# opendeck_mini.net
KiCad netlist of a schematic drawn in EAGLE
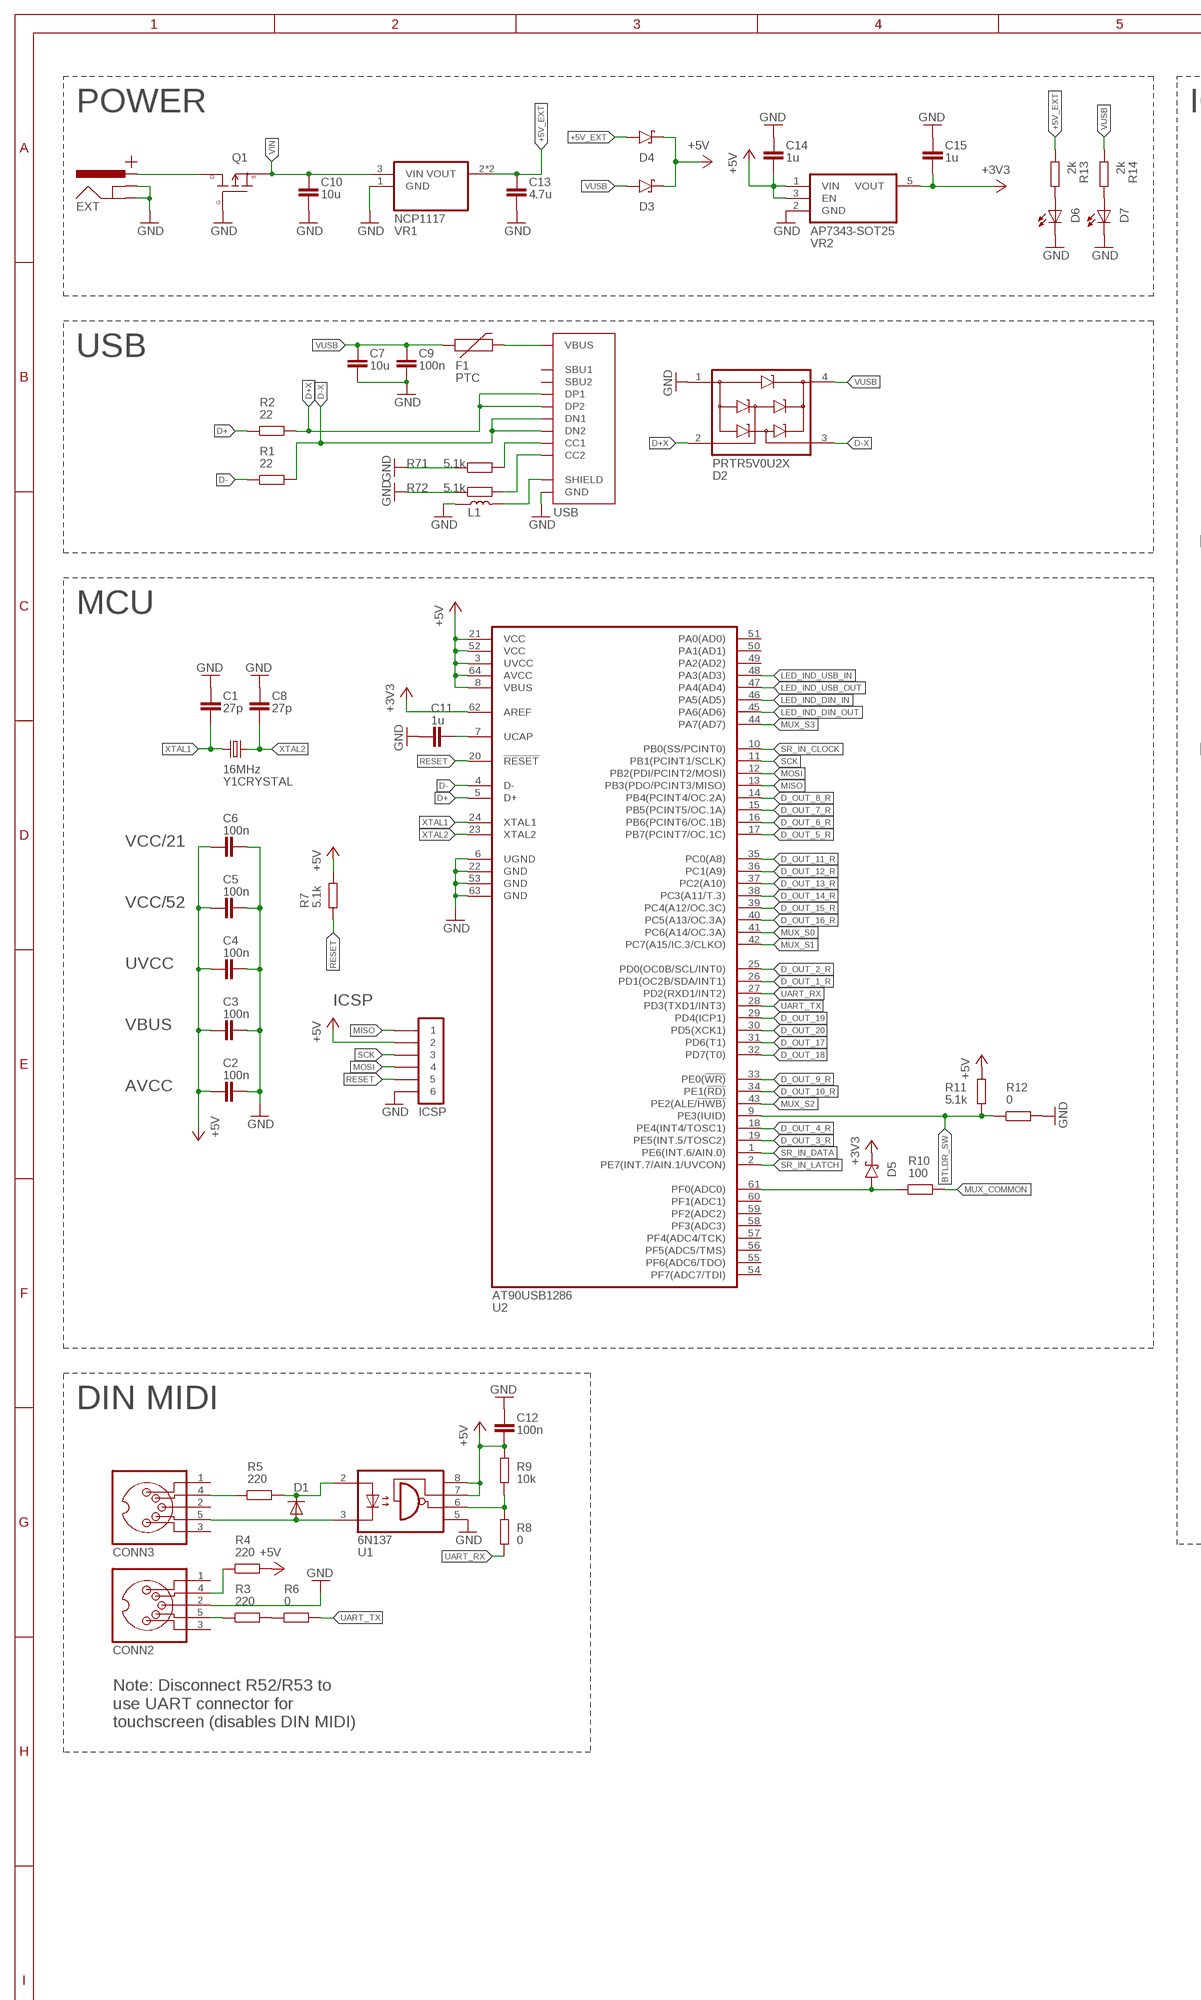
[diagram p0: schematic, sheet 1, part 1 of 2]
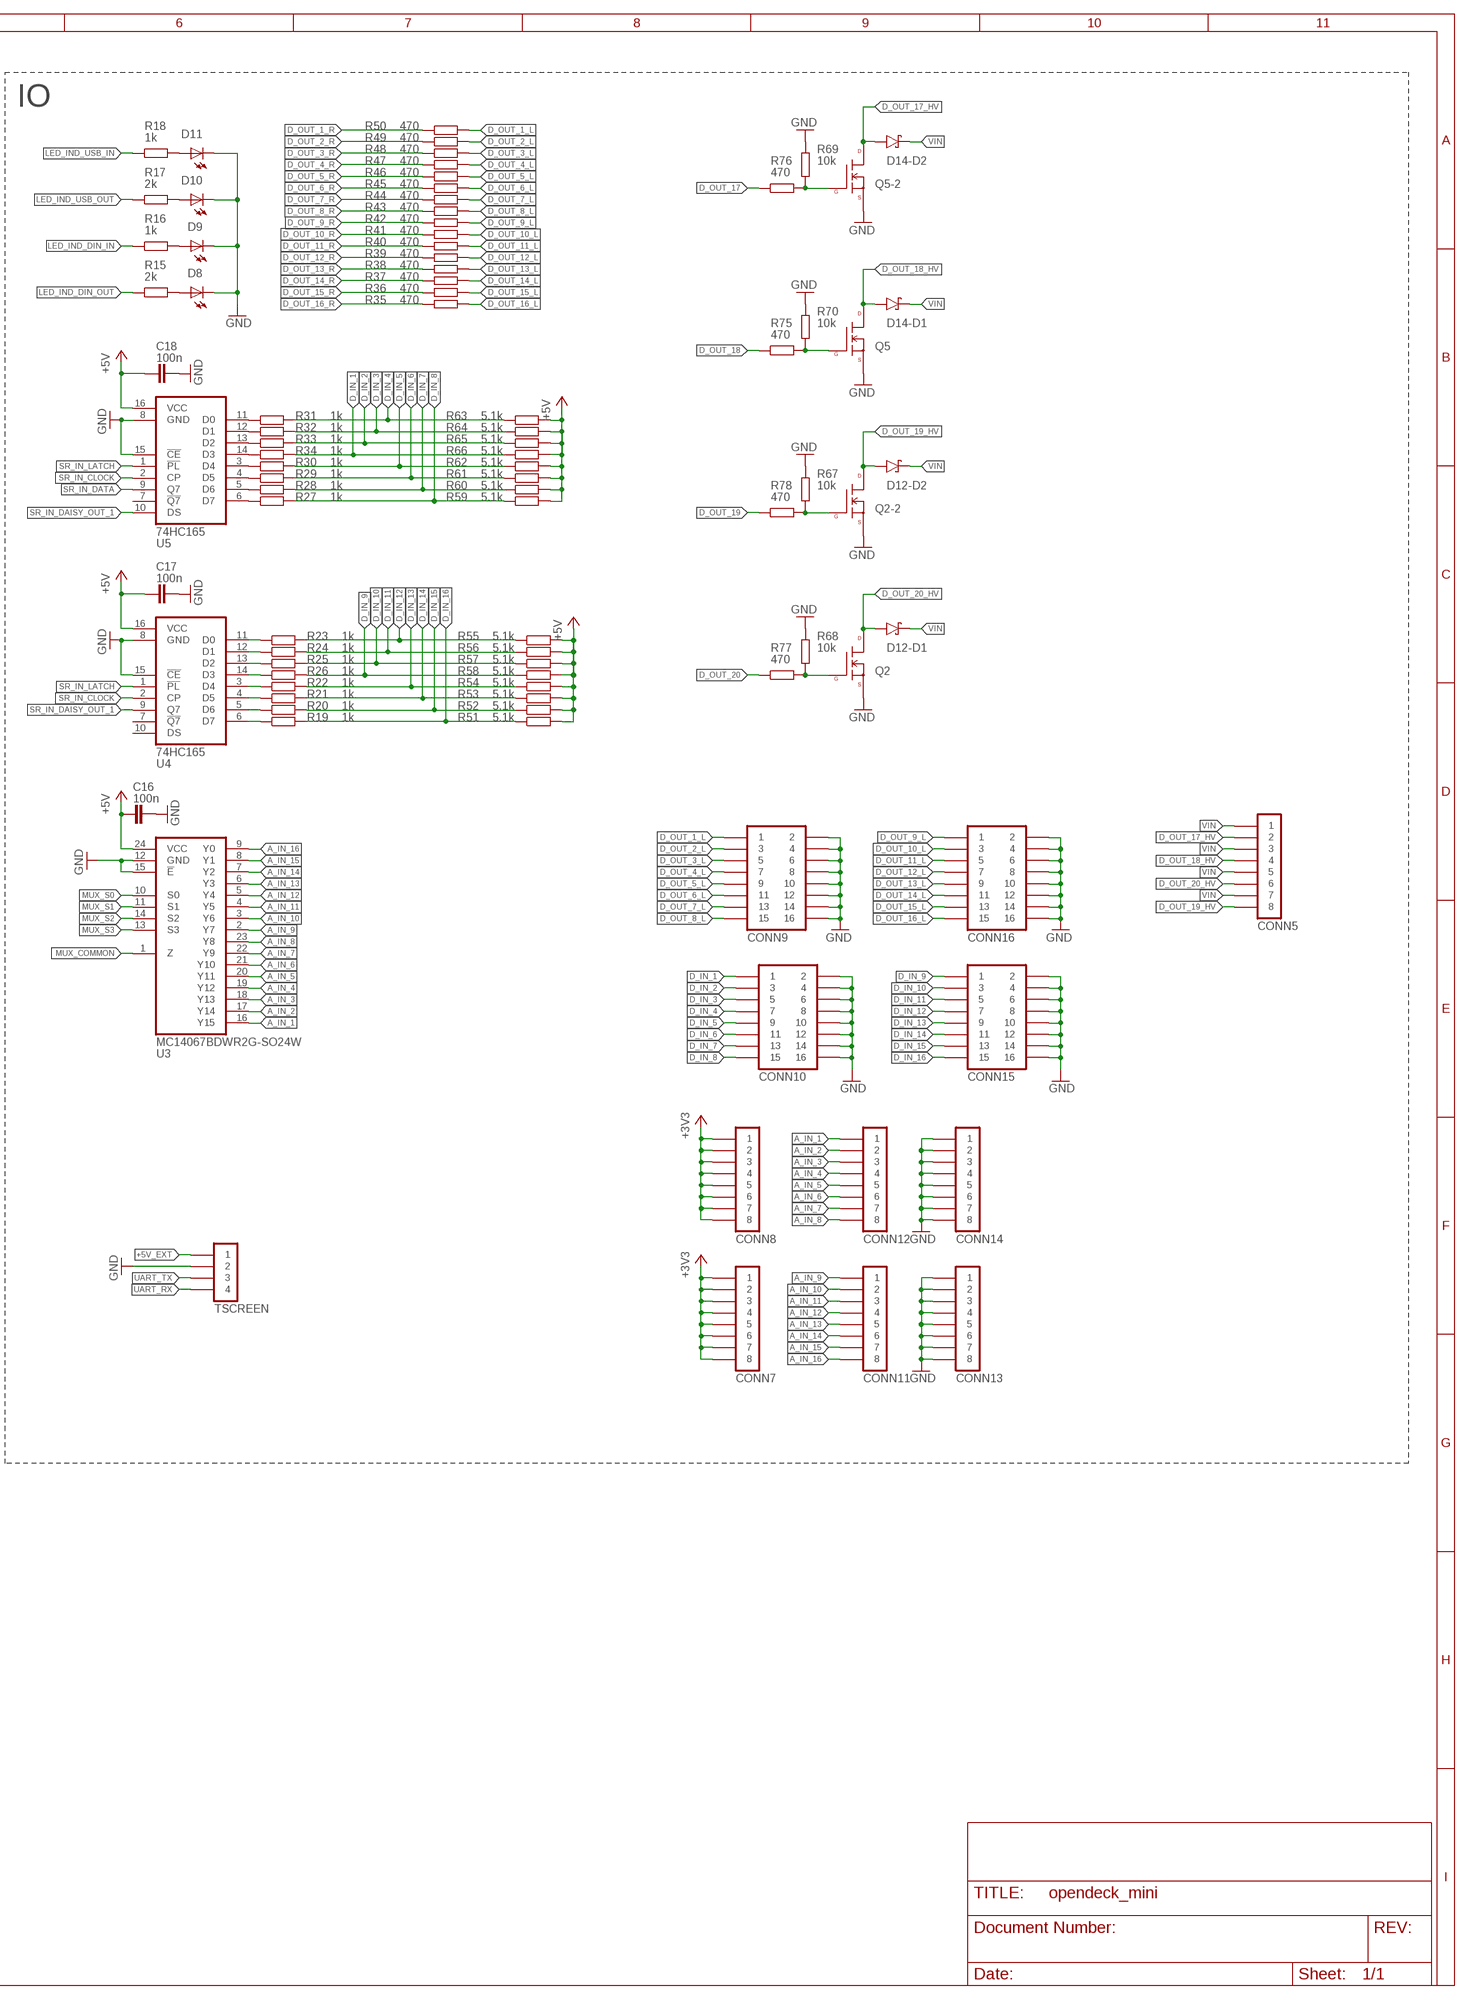
[diagram p1: schematic, sheet 1, part 2 of 2]

(export (version "E")
  (design (tool "Eeschema 10.0.6"))
  (components
    (comp (ref "C1")
      (value "27p")
      (footprint "eagle-import:C0402")
      (libsource (lib "eagle-import") (part "CAPACITOR-0402"))
    )
    (comp (ref "C2")
      (value "100n")
      (footprint "eagle-import:C0402")
      (libsource (lib "eagle-import") (part "CAPACITOR-0402"))
    )
    (comp (ref "C3")
      (value "100n")
      (footprint "eagle-import:C0402")
      (libsource (lib "eagle-import") (part "CAPACITOR-0402"))
    )
    (comp (ref "C4")
      (value "100n")
      (footprint "eagle-import:C0402")
      (libsource (lib "eagle-import") (part "CAPACITOR-0402"))
    )
    (comp (ref "C5")
      (value "100n")
      (footprint "eagle-import:C0402")
      (libsource (lib "eagle-import") (part "CAPACITOR-0402"))
    )
    (comp (ref "C6")
      (value "100n")
      (footprint "eagle-import:C0402")
      (libsource (lib "eagle-import") (part "CAPACITOR-0402"))
    )
    (comp (ref "C7")
      (value "10u")
      (footprint "eagle-import:C0805")
      (libsource (lib "eagle-import") (part "CAPACITOR-0805"))
    )
    (comp (ref "C8")
      (value "27p")
      (footprint "eagle-import:C0402")
      (libsource (lib "eagle-import") (part "CAPACITOR-0402"))
    )
    (comp (ref "C9")
      (value "100n")
      (footprint "eagle-import:C0402")
      (libsource (lib "eagle-import") (part "CAPACITOR-0402"))
    )
    (comp (ref "C10")
      (value "10u")
      (footprint "eagle-import:C0805")
      (libsource (lib "eagle-import") (part "CAPACITOR-0805"))
    )
    (comp (ref "C11")
      (value "1u")
      (footprint "eagle-import:C0603")
      (libsource (lib "eagle-import") (part "CAPACITOR-0603"))
    )
    (comp (ref "C12")
      (value "100n")
      (footprint "eagle-import:C0402")
      (libsource (lib "eagle-import") (part "CAPACITOR-0402"))
    )
    (comp (ref "C13")
      (value "4.7u")
      (footprint "eagle-import:C0603")
      (libsource (lib "eagle-import") (part "CAPACITOR-0603"))
    )
    (comp (ref "C14")
      (value "1u")
      (footprint "eagle-import:C0603")
      (libsource (lib "eagle-import") (part "CAPACITOR-0603"))
    )
    (comp (ref "C15")
      (value "1u")
      (footprint "eagle-import:C0603")
      (libsource (lib "eagle-import") (part "CAPACITOR-0603"))
    )
    (comp (ref "C16")
      (value "100n")
      (footprint "eagle-import:C0402")
      (libsource (lib "eagle-import") (part "CAPACITOR-0402"))
    )
    (comp (ref "C17")
      (value "100n")
      (footprint "eagle-import:C0402")
      (libsource (lib "eagle-import") (part "CAPACITOR-0402"))
    )
    (comp (ref "C18")
      (value "100n")
      (footprint "eagle-import:C0402")
      (libsource (lib "eagle-import") (part "CAPACITOR-0402"))
    )
    (comp (ref "CONN2")
      (value "MIDI_CONN-STD")
      (footprint "eagle-import:DIN5")
      (fields (field (name "MANUFACTURER") "Switchcraft") (field (name "MPN") "57PC5F"))
      (libsource (lib "eagle-import") (part "MIDI_CONN-STD"))
    )
    (comp (ref "CONN3")
      (value "MIDI_CONN-STD")
      (footprint "eagle-import:DIN5")
      (fields (field (name "MANUFACTURER") "Switchcraft") (field (name "MPN") "57PC5F"))
      (libsource (lib "eagle-import") (part "MIDI_CONN-STD"))
    )
    (comp (ref "CONN5")
      (value "PINHD-1X08")
      (footprint "eagle-import:PHOENIX_CONTACT-1984675")
      (fields (field (name "MANUFACTURER") "Phoenix Contact") (field (name "MPN") "1984675"))
      (libsource (lib "eagle-import") (part "PINHD-1X08"))
    )
    (comp (ref "CONN7")
      (value "PINHD-1X08-TH-2.54MM")
      (footprint "eagle-import:1X08-2.54")
      (libsource (lib "eagle-import") (part "PINHD-1X08-TH-2.54MM"))
    )
    (comp (ref "CONN8")
      (value "PINHD-1X08-TH-2.54MM")
      (footprint "eagle-import:1X08-2.54")
      (libsource (lib "eagle-import") (part "PINHD-1X08-TH-2.54MM"))
    )
    (comp (ref "CONN9")
      (value "PINHD-2X08-TH-2.54MM")
      (footprint "eagle-import:2X08-2.54")
      (libsource (lib "eagle-import") (part "PINHD-2X08-TH-2.54MM"))
    )
    (comp (ref "CONN10")
      (value "PINHD-2X08-TH-2.54MM")
      (footprint "eagle-import:2X08-2.54")
      (libsource (lib "eagle-import") (part "PINHD-2X08-TH-2.54MM"))
    )
    (comp (ref "CONN11")
      (value "PINHD-1X08-TH-2.54MM")
      (footprint "eagle-import:1X08-2.54")
      (libsource (lib "eagle-import") (part "PINHD-1X08-TH-2.54MM"))
    )
    (comp (ref "CONN12")
      (value "PINHD-1X08-TH-2.54MM")
      (footprint "eagle-import:1X08-2.54")
      (libsource (lib "eagle-import") (part "PINHD-1X08-TH-2.54MM"))
    )
    (comp (ref "CONN13")
      (value "PINHD-1X08-TH-2.54MM")
      (footprint "eagle-import:1X08-2.54")
      (libsource (lib "eagle-import") (part "PINHD-1X08-TH-2.54MM"))
    )
    (comp (ref "CONN14")
      (value "PINHD-1X08-TH-2.54MM")
      (footprint "eagle-import:1X08-2.54")
      (libsource (lib "eagle-import") (part "PINHD-1X08-TH-2.54MM"))
    )
    (comp (ref "CONN15")
      (value "PINHD-2X08-TH-2.54MM")
      (footprint "eagle-import:2X08-2.54")
      (libsource (lib "eagle-import") (part "PINHD-2X08-TH-2.54MM"))
    )
    (comp (ref "CONN16")
      (value "PINHD-2X08-TH-2.54MM")
      (footprint "eagle-import:2X08-2.54")
      (libsource (lib "eagle-import") (part "PINHD-2X08-TH-2.54MM"))
    )
    (comp (ref "D1")
      (value "1N4148")
      (footprint "eagle-import:SOD-323")
      (fields (field (name "MANUFACTURER") "Comchip Technology") (field (name "MPN") "1N4148WS-HF"))
      (libsource (lib "eagle-import") (part "DIODE-SOD323"))
    )
    (comp (ref "D2")
      (value "PRTR5V0U2X")
      (footprint "eagle-import:SOT143")
      (fields (field (name "MANUFACTURER") "Nexperia"))
      (libsource (lib "eagle-import") (part "PRTR5V0U2X"))
    )
    (comp (ref "D3")
      (value "BAT46INFEON-SOD123")
      (footprint "eagle-import:SOD-123")
      (fields (field (name "MANUFACTURER") "Infineon Technologies") (field (name "MPN") "BAT60AE6327HTSA1"))
      (libsource (lib "eagle-import") (part "BAT46-SOD123INFEON"))
    )
    (comp (ref "D4")
      (value "BAT46INFEON-SOD123")
      (footprint "eagle-import:SOD-123")
      (fields (field (name "MANUFACTURER") "Infineon Technologies") (field (name "MPN") "BAT60AE6327HTSA1"))
      (libsource (lib "eagle-import") (part "BAT46-SOD123INFEON"))
    )
    (comp (ref "D5")
      (value "BAT46-SOT23")
      (footprint "eagle-import:SOT23")
      (fields
        (field (name "MANUFACTURER") "Micro Commercial Components (MCC)")
        (field (name "MPN") "MMBD301-TP")
      )
      (libsource (lib "eagle-import") (part "BAT46-SOT23"))
    )
    (comp (ref "D6")
      (value "Green")
      (footprint "eagle-import:0805_LED")
      (libsource (lib "eagle-import") (part "LED-0805"))
    )
    (comp (ref "D7")
      (value "Blue")
      (footprint "eagle-import:0805_LED")
      (libsource (lib "eagle-import") (part "LED-0805"))
    )
    (comp (ref "D8")
      (value "Red")
      (footprint "eagle-import:0805_LED")
      (libsource (lib "eagle-import") (part "LED-0805"))
    )
    (comp (ref "D9")
      (value "Yellow")
      (footprint "eagle-import:0805_LED")
      (libsource (lib "eagle-import") (part "LED-0805"))
    )
    (comp (ref "D10")
      (value "Red")
      (footprint "eagle-import:0805_LED")
      (libsource (lib "eagle-import") (part "LED-0805"))
    )
    (comp (ref "D11")
      (value "Yellow")
      (footprint "eagle-import:0805_LED")
      (libsource (lib "eagle-import") (part "LED-0805"))
    )
    (comp (ref "D12")
      (value "BAS7007E6327HTSA1")
      (footprint "eagle-import:SOT143")
      (libsource (lib "eagle-import") (part "BAS7007E6327HTSA1"))
    )
    (comp (ref "D14")
      (value "BAS7007E6327HTSA1")
      (footprint "eagle-import:SOT143")
      (libsource (lib "eagle-import") (part "BAS7007E6327HTSA1"))
    )
    (comp (ref "EXT")
      (value "BARREL_JACK")
      (footprint "eagle-import:BARREL_JACK")
      (fields (field (name "MANUFACTURER") "Gravitech") (field (name "MPN") "CON-SOCJ-2155"))
      (libsource (lib "eagle-import") (part "BARREL_JACK"))
    )
    (comp (ref "F1")
      (value "PTC")
      (footprint "eagle-import:L1812")
      (fields (field (name "MANUFACTURER") "Bourns") (field (name "MPN") "MF-MSMF050-2"))
      (libsource (lib "eagle-import") (part "PTC"))
    )
    (comp (ref "ICSP")
      (value "PINHD-2X03-TH-2.54MM-V")
      (footprint "eagle-import:2X03-2.54-V")
      (libsource (lib "eagle-import") (part "PINHD-2X03-TH-2.54MM-V"))
    )
    (comp (ref "L1")
      (value "FERRITE_BEAD-BLM21PG221SN1D")
      (footprint "eagle-import:L0805")
      (fields (field (name "MANUFACTURER") "Murata") (field (name "MPN") "BLM21PG221SN1D"))
      (libsource (lib "eagle-import") (part "FERRITE_BEAD-BLM21PG221SN1D"))
    )
    (comp (ref "Q1")
      (value "BSS314PEH6327XTSA1")
      (footprint "eagle-import:SOT23")
      (fields (field (name "MANUFACTURER") "Infineon Technologies"))
      (libsource (lib "eagle-import") (part "BSS314PEH6327XTSA1"))
    )
    (comp (ref "Q2")
      (value "NTGD3148N")
      (footprint "eagle-import:TSOP-6")
      (fields (field (name "MANUFACTURER") "ON Semiconductor") (field (name "MPN") "NTGD3148NT1G"))
      (libsource (lib "eagle-import") (part "NTGD3148N"))
    )
    (comp (ref "Q5")
      (value "NTGD3148N")
      (footprint "eagle-import:TSOP-6")
      (fields (field (name "MANUFACTURER") "ON Semiconductor") (field (name "MPN") "NTGD3148NT1G"))
      (libsource (lib "eagle-import") (part "NTGD3148N"))
    )
    (comp (ref "R1")
      (value "22")
      (footprint "eagle-import:R0402")
      (libsource (lib "eagle-import") (part "RESISTOR-0402"))
    )
    (comp (ref "R2")
      (value "22")
      (footprint "eagle-import:R0402")
      (libsource (lib "eagle-import") (part "RESISTOR-0402"))
    )
    (comp (ref "R3")
      (value "220")
      (footprint "eagle-import:R0402")
      (libsource (lib "eagle-import") (part "RESISTOR-0402"))
    )
    (comp (ref "R4")
      (value "220")
      (footprint "eagle-import:R0402")
      (libsource (lib "eagle-import") (part "RESISTOR-0402"))
    )
    (comp (ref "R5")
      (value "220")
      (footprint "eagle-import:R0402")
      (libsource (lib "eagle-import") (part "RESISTOR-0402"))
    )
    (comp (ref "R6")
      (value "0")
      (footprint "eagle-import:1X02-2.54-V")
      (libsource (lib "eagle-import") (part "RESISTOR-TH-2.54"))
    )
    (comp (ref "R7")
      (value "5.1k")
      (footprint "eagle-import:R0402")
      (libsource (lib "eagle-import") (part "RESISTOR-0402"))
    )
    (comp (ref "R8")
      (value "0")
      (footprint "eagle-import:1X02-2.54-V")
      (libsource (lib "eagle-import") (part "RESISTOR-TH-2.54"))
    )
    (comp (ref "R9")
      (value "10k")
      (footprint "eagle-import:R0402")
      (libsource (lib "eagle-import") (part "RESISTOR-0402"))
    )
    (comp (ref "R10")
      (value "100")
      (footprint "eagle-import:R0402")
      (libsource (lib "eagle-import") (part "RESISTOR-0402"))
    )
    (comp (ref "R11")
      (value "5.1k")
      (footprint "eagle-import:R0402")
      (libsource (lib "eagle-import") (part "RESISTOR-0402"))
    )
    (comp (ref "R12")
      (value "0")
      (footprint "eagle-import:1X02-2.54-V")
      (libsource (lib "eagle-import") (part "RESISTOR-TH-2.54"))
    )
    (comp (ref "R13")
      (value "2k")
      (footprint "eagle-import:R0402")
      (libsource (lib "eagle-import") (part "RESISTOR-0402"))
    )
    (comp (ref "R14")
      (value "2k")
      (footprint "eagle-import:R0402")
      (libsource (lib "eagle-import") (part "RESISTOR-0402"))
    )
    (comp (ref "R15")
      (value "2k")
      (footprint "eagle-import:R0402")
      (libsource (lib "eagle-import") (part "RESISTOR-0402"))
    )
    (comp (ref "R16")
      (value "1k")
      (footprint "eagle-import:R0402")
      (libsource (lib "eagle-import") (part "RESISTOR-0402"))
    )
    (comp (ref "R17")
      (value "2k")
      (footprint "eagle-import:R0402")
      (libsource (lib "eagle-import") (part "RESISTOR-0402"))
    )
    (comp (ref "R18")
      (value "1k")
      (footprint "eagle-import:R0402")
      (libsource (lib "eagle-import") (part "RESISTOR-0402"))
    )
    (comp (ref "R19")
      (value "1k")
      (footprint "eagle-import:R0402")
      (libsource (lib "eagle-import") (part "RESISTOR-0402"))
    )
    (comp (ref "R20")
      (value "1k")
      (footprint "eagle-import:R0402")
      (libsource (lib "eagle-import") (part "RESISTOR-0402"))
    )
    (comp (ref "R21")
      (value "1k")
      (footprint "eagle-import:R0402")
      (libsource (lib "eagle-import") (part "RESISTOR-0402"))
    )
    (comp (ref "R22")
      (value "1k")
      (footprint "eagle-import:R0402")
      (libsource (lib "eagle-import") (part "RESISTOR-0402"))
    )
    (comp (ref "R23")
      (value "1k")
      (footprint "eagle-import:R0402")
      (libsource (lib "eagle-import") (part "RESISTOR-0402"))
    )
    (comp (ref "R24")
      (value "1k")
      (footprint "eagle-import:R0402")
      (libsource (lib "eagle-import") (part "RESISTOR-0402"))
    )
    (comp (ref "R25")
      (value "1k")
      (footprint "eagle-import:R0402")
      (libsource (lib "eagle-import") (part "RESISTOR-0402"))
    )
    (comp (ref "R26")
      (value "1k")
      (footprint "eagle-import:R0402")
      (libsource (lib "eagle-import") (part "RESISTOR-0402"))
    )
    (comp (ref "R27")
      (value "1k")
      (footprint "eagle-import:R0402")
      (libsource (lib "eagle-import") (part "RESISTOR-0402"))
    )
    (comp (ref "R28")
      (value "1k")
      (footprint "eagle-import:R0402")
      (libsource (lib "eagle-import") (part "RESISTOR-0402"))
    )
    (comp (ref "R29")
      (value "1k")
      (footprint "eagle-import:R0402")
      (libsource (lib "eagle-import") (part "RESISTOR-0402"))
    )
    (comp (ref "R30")
      (value "1k")
      (footprint "eagle-import:R0402")
      (libsource (lib "eagle-import") (part "RESISTOR-0402"))
    )
    (comp (ref "R31")
      (value "1k")
      (footprint "eagle-import:R0402")
      (libsource (lib "eagle-import") (part "RESISTOR-0402"))
    )
    (comp (ref "R32")
      (value "1k")
      (footprint "eagle-import:R0402")
      (libsource (lib "eagle-import") (part "RESISTOR-0402"))
    )
    (comp (ref "R33")
      (value "1k")
      (footprint "eagle-import:R0402")
      (libsource (lib "eagle-import") (part "RESISTOR-0402"))
    )
    (comp (ref "R34")
      (value "1k")
      (footprint "eagle-import:R0402")
      (libsource (lib "eagle-import") (part "RESISTOR-0402"))
    )
    (comp (ref "R35")
      (value "470")
      (footprint "eagle-import:R0402")
      (libsource (lib "eagle-import") (part "RESISTOR-0402"))
    )
    (comp (ref "R36")
      (value "470")
      (footprint "eagle-import:R0402")
      (libsource (lib "eagle-import") (part "RESISTOR-0402"))
    )
    (comp (ref "R37")
      (value "470")
      (footprint "eagle-import:R0402")
      (libsource (lib "eagle-import") (part "RESISTOR-0402"))
    )
    (comp (ref "R38")
      (value "470")
      (footprint "eagle-import:R0402")
      (libsource (lib "eagle-import") (part "RESISTOR-0402"))
    )
    (comp (ref "R39")
      (value "470")
      (footprint "eagle-import:R0402")
      (libsource (lib "eagle-import") (part "RESISTOR-0402"))
    )
    (comp (ref "R40")
      (value "470")
      (footprint "eagle-import:R0402")
      (libsource (lib "eagle-import") (part "RESISTOR-0402"))
    )
    (comp (ref "R41")
      (value "470")
      (footprint "eagle-import:R0402")
      (libsource (lib "eagle-import") (part "RESISTOR-0402"))
    )
    (comp (ref "R42")
      (value "470")
      (footprint "eagle-import:R0402")
      (libsource (lib "eagle-import") (part "RESISTOR-0402"))
    )
    (comp (ref "R43")
      (value "470")
      (footprint "eagle-import:R0402")
      (libsource (lib "eagle-import") (part "RESISTOR-0402"))
    )
    (comp (ref "R44")
      (value "470")
      (footprint "eagle-import:R0402")
      (libsource (lib "eagle-import") (part "RESISTOR-0402"))
    )
    (comp (ref "R45")
      (value "470")
      (footprint "eagle-import:R0402")
      (libsource (lib "eagle-import") (part "RESISTOR-0402"))
    )
    (comp (ref "R46")
      (value "470")
      (footprint "eagle-import:R0402")
      (libsource (lib "eagle-import") (part "RESISTOR-0402"))
    )
    (comp (ref "R47")
      (value "470")
      (footprint "eagle-import:R0402")
      (libsource (lib "eagle-import") (part "RESISTOR-0402"))
    )
    (comp (ref "R48")
      (value "470")
      (footprint "eagle-import:R0402")
      (libsource (lib "eagle-import") (part "RESISTOR-0402"))
    )
    (comp (ref "R49")
      (value "470")
      (footprint "eagle-import:R0402")
      (libsource (lib "eagle-import") (part "RESISTOR-0402"))
    )
    (comp (ref "R50")
      (value "470")
      (footprint "eagle-import:R0402")
      (libsource (lib "eagle-import") (part "RESISTOR-0402"))
    )
    (comp (ref "R51")
      (value "5.1k")
      (footprint "eagle-import:R0402")
      (libsource (lib "eagle-import") (part "RESISTOR-0402"))
    )
    (comp (ref "R52")
      (value "5.1k")
      (footprint "eagle-import:R0402")
      (libsource (lib "eagle-import") (part "RESISTOR-0402"))
    )
    (comp (ref "R53")
      (value "5.1k")
      (footprint "eagle-import:R0402")
      (libsource (lib "eagle-import") (part "RESISTOR-0402"))
    )
    (comp (ref "R54")
      (value "5.1k")
      (footprint "eagle-import:R0402")
      (libsource (lib "eagle-import") (part "RESISTOR-0402"))
    )
    (comp (ref "R55")
      (value "5.1k")
      (footprint "eagle-import:R0402")
      (libsource (lib "eagle-import") (part "RESISTOR-0402"))
    )
    (comp (ref "R56")
      (value "5.1k")
      (footprint "eagle-import:R0402")
      (libsource (lib "eagle-import") (part "RESISTOR-0402"))
    )
    (comp (ref "R57")
      (value "5.1k")
      (footprint "eagle-import:R0402")
      (libsource (lib "eagle-import") (part "RESISTOR-0402"))
    )
    (comp (ref "R58")
      (value "5.1k")
      (footprint "eagle-import:R0402")
      (libsource (lib "eagle-import") (part "RESISTOR-0402"))
    )
    (comp (ref "R59")
      (value "5.1k")
      (footprint "eagle-import:R0402")
      (libsource (lib "eagle-import") (part "RESISTOR-0402"))
    )
    (comp (ref "R60")
      (value "5.1k")
      (footprint "eagle-import:R0402")
      (libsource (lib "eagle-import") (part "RESISTOR-0402"))
    )
    (comp (ref "R61")
      (value "5.1k")
      (footprint "eagle-import:R0402")
      (libsource (lib "eagle-import") (part "RESISTOR-0402"))
    )
    (comp (ref "R62")
      (value "5.1k")
      (footprint "eagle-import:R0402")
      (libsource (lib "eagle-import") (part "RESISTOR-0402"))
    )
    (comp (ref "R63")
      (value "5.1k")
      (footprint "eagle-import:R0402")
      (libsource (lib "eagle-import") (part "RESISTOR-0402"))
    )
    (comp (ref "R64")
      (value "5.1k")
      (footprint "eagle-import:R0402")
      (libsource (lib "eagle-import") (part "RESISTOR-0402"))
    )
    (comp (ref "R65")
      (value "5.1k")
      (footprint "eagle-import:R0402")
      (libsource (lib "eagle-import") (part "RESISTOR-0402"))
    )
    (comp (ref "R66")
      (value "5.1k")
      (footprint "eagle-import:R0402")
      (libsource (lib "eagle-import") (part "RESISTOR-0402"))
    )
    (comp (ref "R67")
      (value "10k")
      (footprint "eagle-import:R0402")
      (libsource (lib "eagle-import") (part "RESISTOR-0402"))
    )
    (comp (ref "R68")
      (value "10k")
      (footprint "eagle-import:R0402")
      (libsource (lib "eagle-import") (part "RESISTOR-0402"))
    )
    (comp (ref "R69")
      (value "10k")
      (footprint "eagle-import:R0402")
      (libsource (lib "eagle-import") (part "RESISTOR-0402"))
    )
    (comp (ref "R70")
      (value "10k")
      (footprint "eagle-import:R0402")
      (libsource (lib "eagle-import") (part "RESISTOR-0402"))
    )
    (comp (ref "R71")
      (value "5.1k")
      (footprint "eagle-import:R0402")
      (libsource (lib "eagle-import") (part "RESISTOR-0402"))
    )
    (comp (ref "R72")
      (value "5.1k")
      (footprint "eagle-import:R0402")
      (libsource (lib "eagle-import") (part "RESISTOR-0402"))
    )
    (comp (ref "R75")
      (value "470")
      (footprint "eagle-import:R0402")
      (libsource (lib "eagle-import") (part "RESISTOR-0402"))
    )
    (comp (ref "R76")
      (value "470")
      (footprint "eagle-import:R0402")
      (libsource (lib "eagle-import") (part "RESISTOR-0402"))
    )
    (comp (ref "R77")
      (value "470")
      (footprint "eagle-import:R0402")
      (libsource (lib "eagle-import") (part "RESISTOR-0402"))
    )
    (comp (ref "R78")
      (value "470")
      (footprint "eagle-import:R0402")
      (libsource (lib "eagle-import") (part "RESISTOR-0402"))
    )
    (comp (ref "TSCREEN")
      (value "PINHD-1X04-TH-2.54MM")
      (footprint "eagle-import:1X04-2.54")
      (libsource (lib "eagle-import") (part "PINHD-1X04-TH-2.54MM"))
    )
    (comp (ref "U1")
      (value "6N137")
      (footprint "eagle-import:DIL08")
      (fields (field (name "MANUFACTURER") "Vishay"))
      (libsource (lib "eagle-import") (part "6N137"))
    )
    (comp (ref "U2")
      (value "AT90USB1286")
      (footprint "eagle-import:TQFP-64-14X14")
      (fields (field (name "MANUFACTURER") "Microchip/Atmel") (field (name "MPN") "AT90USB1286-AU"))
      (libsource (lib "eagle-import") (part "AT90USB1286"))
    )
    (comp (ref "U3")
      (value "MC14067BDWR2G-SO24W")
      (footprint "eagle-import:SO24-W")
      (fields (field (name "MANUFACTURER") "ON Semiconductor") (field (name "MPN") "MC14067BDWR2G"))
      (libsource (lib "eagle-import") (part "MC14067BDWR2G-SO24W"))
    )
    (comp (ref "U4")
      (value "74HC165")
      (footprint "eagle-import:SO16")
      (fields (field (name "MANUFACTURER") "Nexperia") (field (name "MPN") "74HC165D"))
      (libsource (lib "eagle-import") (part "74165HC"))
    )
    (comp (ref "U5")
      (value "74HC165")
      (footprint "eagle-import:SO16")
      (fields (field (name "MANUFACTURER") "Nexperia") (field (name "MPN") "74HC165D"))
      (libsource (lib "eagle-import") (part "74165HC"))
    )
    (comp (ref "USB")
      (value "USB-C")
      (footprint "eagle-import:GCT-USB4085-GF-A")
      (fields (field (name "MANUFACTURER") "GCT") (field (name "MPN") "USB4085-GF-A"))
      (libsource (lib "eagle-import") (part "USB-C"))
    )
    (comp (ref "VR1")
      (value "NCP1117")
      (footprint "eagle-import:SOT223")
      (fields (field (name "MANUFACTURER") "ON Semiconductor") (field (name "MPN") "NCP1117ST50T3G"))
      (libsource (lib "eagle-import") (part "NCP1117"))
    )
    (comp (ref "VR2")
      (value "AP7343-SOT25")
      (footprint "eagle-import:SOT25")
      (fields (field (name "MANUFACTURER") "Diodes Incorporated") (field (name "MPN") "AP7343-33W5-7"))
      (libsource (lib "eagle-import") (part "AP7343-SOT25"))
    )
    (comp (ref "Y1")
      (value "16MHz")
      (footprint "eagle-import:CRYSTAL-SMD-3.2X2.5")
      (fields (field (name "MANUFACTURER") "Epson") (field (name "MPN") "X1E0000210120 TSX-3225 16MHZ 16PF"))
      (libsource (lib "eagle-import") (part "CRYSTAL-4P-SMD-3.2X2.5"))
    )
  )
  (nets
    (net (code "1") (name "+3V3") (class "Default")
      (node (ref "C15") (pin "2") (pinfunction "2_2") (pintype "passive"))
      (node (ref "CONN7") (pin "1") (pinfunction "1_1") (pintype "passive"))
      (node (ref "CONN7") (pin "2") (pinfunction "2_2") (pintype "passive"))
      (node (ref "CONN7") (pin "3") (pinfunction "3_3") (pintype "passive"))
      (node (ref "CONN7") (pin "4") (pinfunction "4_4") (pintype "passive"))
      (node (ref "CONN7") (pin "5") (pinfunction "5_5") (pintype "passive"))
      (node (ref "CONN7") (pin "6") (pinfunction "6_6") (pintype "passive"))
      (node (ref "CONN7") (pin "7") (pinfunction "7_7") (pintype "passive"))
      (node (ref "CONN7") (pin "8") (pinfunction "8_8") (pintype "passive"))
      (node (ref "CONN8") (pin "1") (pinfunction "1_1") (pintype "passive"))
      (node (ref "CONN8") (pin "2") (pinfunction "2_2") (pintype "passive"))
      (node (ref "CONN8") (pin "3") (pinfunction "3_3") (pintype "passive"))
      (node (ref "CONN8") (pin "4") (pinfunction "4_4") (pintype "passive"))
      (node (ref "CONN8") (pin "5") (pinfunction "5_5") (pintype "passive"))
      (node (ref "CONN8") (pin "6") (pinfunction "6_6") (pintype "passive"))
      (node (ref "CONN8") (pin "7") (pinfunction "7_7") (pintype "passive"))
      (node (ref "CONN8") (pin "8") (pinfunction "8_8") (pintype "passive"))
      (node (ref "D5") (pin "3") (pinfunction "C_3") (pintype "passive"))
      (node (ref "U2") (pin "62") (pinfunction "AREF_62") (pintype "power_in"))
      (node (ref "VR2") (pin "5") (pinfunction "VOUT_5") (pintype "passive"))
    )
    (net (code "2") (name "+5V") (class "Default")
      (node (ref "C12") (pin "2") (pinfunction "2_2") (pintype "passive"))
      (node (ref "C14") (pin "2") (pinfunction "2_2") (pintype "passive"))
      (node (ref "C16") (pin "1") (pinfunction "1_1") (pintype "passive"))
      (node (ref "C17") (pin "1") (pinfunction "1_1") (pintype "passive"))
      (node (ref "C18") (pin "1") (pinfunction "1_1") (pintype "passive"))
      (node (ref "C2") (pin "1") (pinfunction "1_1") (pintype "passive"))
      (node (ref "C3") (pin "1") (pinfunction "1_1") (pintype "passive"))
      (node (ref "C4") (pin "1") (pinfunction "1_1") (pintype "passive"))
      (node (ref "C5") (pin "1") (pinfunction "1_1") (pintype "passive"))
      (node (ref "C6") (pin "1") (pinfunction "1_1") (pintype "passive"))
      (node (ref "D3") (pin "C") (pinfunction "C_C") (pintype "passive"))
      (node (ref "D4") (pin "C") (pinfunction "C_C") (pintype "passive"))
      (node (ref "ICSP") (pin "2") (pinfunction "2_2") (pintype "passive"))
      (node (ref "R11") (pin "2") (pinfunction "2_2") (pintype "passive"))
      (node (ref "R4") (pin "2") (pinfunction "2_2") (pintype "passive"))
      (node (ref "R51") (pin "2") (pinfunction "2_2") (pintype "passive"))
      (node (ref "R52") (pin "2") (pinfunction "2_2") (pintype "passive"))
      (node (ref "R53") (pin "2") (pinfunction "2_2") (pintype "passive"))
      (node (ref "R54") (pin "2") (pinfunction "2_2") (pintype "passive"))
      (node (ref "R55") (pin "2") (pinfunction "2_2") (pintype "passive"))
      (node (ref "R56") (pin "2") (pinfunction "2_2") (pintype "passive"))
      (node (ref "R57") (pin "2") (pinfunction "2_2") (pintype "passive"))
      (node (ref "R58") (pin "2") (pinfunction "2_2") (pintype "passive"))
      (node (ref "R59") (pin "2") (pinfunction "2_2") (pintype "passive"))
      (node (ref "R60") (pin "2") (pinfunction "2_2") (pintype "passive"))
      (node (ref "R61") (pin "2") (pinfunction "2_2") (pintype "passive"))
      (node (ref "R62") (pin "2") (pinfunction "2_2") (pintype "passive"))
      (node (ref "R63") (pin "2") (pinfunction "2_2") (pintype "passive"))
      (node (ref "R64") (pin "2") (pinfunction "2_2") (pintype "passive"))
      (node (ref "R65") (pin "2") (pinfunction "2_2") (pintype "passive"))
      (node (ref "R66") (pin "2") (pinfunction "2_2") (pintype "passive"))
      (node (ref "R7") (pin "2") (pinfunction "2_2") (pintype "passive"))
      (node (ref "R9") (pin "2") (pinfunction "2_2") (pintype "passive"))
      (node (ref "U1") (pin "7") (pinfunction "VE_7") (pintype "input"))
      (node (ref "U1") (pin "8") (pinfunction "VCC_8") (pintype "power_in"))
      (node (ref "U2") (pin "21") (pinfunction "VCC_21") (pintype "power_in"))
      (node (ref "U2") (pin "3") (pinfunction "UVCC_3") (pintype "power_in"))
      (node (ref "U2") (pin "52") (pinfunction "VCC_52") (pintype "power_in"))
      (node (ref "U2") (pin "64") (pinfunction "AVCC_64") (pintype "power_in"))
      (node (ref "U2") (pin "8") (pinfunction "VBUS_8") (pintype "power_in"))
      (node (ref "U3") (pin "24") (pinfunction "VCC_24") (pintype "passive"))
      (node (ref "U4") (pin "16") (pinfunction "VCC_16") (pintype "power_in"))
      (node (ref "U5") (pin "16") (pinfunction "VCC_16") (pintype "power_in"))
      (node (ref "VR2") (pin "1") (pinfunction "VIN_1") (pintype "passive"))
      (node (ref "VR2") (pin "3") (pinfunction "EN_3") (pintype "passive"))
    )
    (net (code "3") (name "+5V_EXT") (class "Default")
      (node (ref "C13") (pin "1") (pinfunction "1_1") (pintype "passive"))
      (node (ref "D4") (pin "A") (pinfunction "A_A") (pintype "passive"))
      (node (ref "R13") (pin "1") (pinfunction "1_1") (pintype "passive"))
      (node (ref "TSCREEN") (pin "1") (pinfunction "1_1") (pintype "passive"))
      (node (ref "VR1") (pin "2") (pinfunction "VOUT_2") (pintype "passive"))
      (node (ref "VR1") (pin "4") (pinfunction "VOUT_4") (pintype "passive"))
    )
    (net (code "4") (name "A_IN_1") (class "Default")
      (node (ref "CONN12") (pin "1") (pinfunction "1_1") (pintype "passive"))
      (node (ref "U3") (pin "16") (pinfunction "Y15_16") (pintype "bidirectional"))
    )
    (net (code "5") (name "A_IN_2") (class "Default")
      (node (ref "CONN12") (pin "2") (pinfunction "2_2") (pintype "passive"))
      (node (ref "U3") (pin "17") (pinfunction "Y14_17") (pintype "bidirectional"))
    )
    (net (code "6") (name "A_IN_3") (class "Default")
      (node (ref "CONN12") (pin "3") (pinfunction "3_3") (pintype "passive"))
      (node (ref "U3") (pin "18") (pinfunction "Y13_18") (pintype "bidirectional"))
    )
    (net (code "7") (name "A_IN_4") (class "Default")
      (node (ref "CONN12") (pin "4") (pinfunction "4_4") (pintype "passive"))
      (node (ref "U3") (pin "19") (pinfunction "Y12_19") (pintype "bidirectional"))
    )
    (net (code "8") (name "A_IN_5") (class "Default")
      (node (ref "CONN12") (pin "5") (pinfunction "5_5") (pintype "passive"))
      (node (ref "U3") (pin "20") (pinfunction "Y11_20") (pintype "bidirectional"))
    )
    (net (code "9") (name "A_IN_6") (class "Default")
      (node (ref "CONN12") (pin "6") (pinfunction "6_6") (pintype "passive"))
      (node (ref "U3") (pin "21") (pinfunction "Y10_21") (pintype "bidirectional"))
    )
    (net (code "10") (name "A_IN_7") (class "Default")
      (node (ref "CONN12") (pin "7") (pinfunction "7_7") (pintype "passive"))
      (node (ref "U3") (pin "22") (pinfunction "Y9_22") (pintype "bidirectional"))
    )
    (net (code "11") (name "A_IN_8") (class "Default")
      (node (ref "CONN12") (pin "8") (pinfunction "8_8") (pintype "passive"))
      (node (ref "U3") (pin "23") (pinfunction "Y8_23") (pintype "bidirectional"))
    )
    (net (code "12") (name "A_IN_9") (class "Default")
      (node (ref "CONN11") (pin "1") (pinfunction "1_1") (pintype "passive"))
      (node (ref "U3") (pin "2") (pinfunction "Y7_2") (pintype "bidirectional"))
    )
    (net (code "13") (name "A_IN_10") (class "Default")
      (node (ref "CONN11") (pin "2") (pinfunction "2_2") (pintype "passive"))
      (node (ref "U3") (pin "3") (pinfunction "Y6_3") (pintype "bidirectional"))
    )
    (net (code "14") (name "A_IN_11") (class "Default")
      (node (ref "CONN11") (pin "3") (pinfunction "3_3") (pintype "passive"))
      (node (ref "U3") (pin "4") (pinfunction "Y5_4") (pintype "bidirectional"))
    )
    (net (code "15") (name "A_IN_12") (class "Default")
      (node (ref "CONN11") (pin "4") (pinfunction "4_4") (pintype "passive"))
      (node (ref "U3") (pin "5") (pinfunction "Y4_5") (pintype "bidirectional"))
    )
    (net (code "16") (name "A_IN_13") (class "Default")
      (node (ref "CONN11") (pin "5") (pinfunction "5_5") (pintype "passive"))
      (node (ref "U3") (pin "6") (pinfunction "Y3_6") (pintype "bidirectional"))
    )
    (net (code "17") (name "A_IN_14") (class "Default")
      (node (ref "CONN11") (pin "6") (pinfunction "6_6") (pintype "passive"))
      (node (ref "U3") (pin "7") (pinfunction "Y2_7") (pintype "bidirectional"))
    )
    (net (code "18") (name "A_IN_15") (class "Default")
      (node (ref "CONN11") (pin "7") (pinfunction "7_7") (pintype "passive"))
      (node (ref "U3") (pin "8") (pinfunction "Y1_8") (pintype "bidirectional"))
    )
    (net (code "19") (name "A_IN_16") (class "Default")
      (node (ref "CONN11") (pin "8") (pinfunction "8_8") (pintype "passive"))
      (node (ref "U3") (pin "9") (pinfunction "Y0_9") (pintype "bidirectional"))
    )
    (net (code "20") (name "BTLDR_SW") (class "Default")
      (node (ref "R11") (pin "1") (pinfunction "1_1") (pintype "passive"))
      (node (ref "R12") (pin "1") (pinfunction "1_1") (pintype "passive"))
      (node (ref "U2") (pin "9") (pinfunction "PE3(IUID)_9") (pintype "bidirectional"))
    )
    (net (code "21") (name "D+") (class "Default")
      (node (ref "R2") (pin "1") (pinfunction "1_1") (pintype "passive"))
      (node (ref "U2") (pin "5") (pinfunction "D+_5") (pintype "bidirectional"))
    )
    (net (code "22") (name "D+X") (class "Default")
      (node (ref "D2") (pin "2") (pinfunction "I/O1_2") (pintype "passive"))
      (node (ref "R2") (pin "2") (pinfunction "2_2") (pintype "passive"))
      (node (ref "USB") (pin "A6") (pinfunction "DP1_A6") (pintype "bidirectional"))
      (node (ref "USB") (pin "B6") (pinfunction "DP2_B6") (pintype "bidirectional"))
    )
    (net (code "23") (name "D-") (class "Default")
      (node (ref "R1") (pin "1") (pinfunction "1_1") (pintype "passive"))
      (node (ref "U2") (pin "4") (pinfunction "D-_4") (pintype "bidirectional"))
    )
    (net (code "24") (name "D-X") (class "Default")
      (node (ref "D2") (pin "3") (pinfunction "I/O2_3") (pintype "passive"))
      (node (ref "R1") (pin "2") (pinfunction "2_2") (pintype "passive"))
      (node (ref "USB") (pin "A7") (pinfunction "DN1_A7") (pintype "bidirectional"))
      (node (ref "USB") (pin "B7") (pinfunction "DN2_B7") (pintype "bidirectional"))
    )
    (net (code "25") (name "D_IN_1") (class "Default")
      (node (ref "CONN10") (pin "1") (pinfunction "1_1") (pintype "passive"))
      (node (ref "R34") (pin "2") (pinfunction "2_2") (pintype "passive"))
      (node (ref "R66") (pin "1") (pinfunction "1_1") (pintype "passive"))
    )
    (net (code "26") (name "D_IN_2") (class "Default")
      (node (ref "CONN10") (pin "3") (pinfunction "3_3") (pintype "passive"))
      (node (ref "R33") (pin "2") (pinfunction "2_2") (pintype "passive"))
      (node (ref "R65") (pin "1") (pinfunction "1_1") (pintype "passive"))
    )
    (net (code "27") (name "D_IN_3") (class "Default")
      (node (ref "CONN10") (pin "5") (pinfunction "5_5") (pintype "passive"))
      (node (ref "R32") (pin "2") (pinfunction "2_2") (pintype "passive"))
      (node (ref "R64") (pin "1") (pinfunction "1_1") (pintype "passive"))
    )
    (net (code "28") (name "D_IN_4") (class "Default")
      (node (ref "CONN10") (pin "7") (pinfunction "7_7") (pintype "passive"))
      (node (ref "R31") (pin "2") (pinfunction "2_2") (pintype "passive"))
      (node (ref "R63") (pin "1") (pinfunction "1_1") (pintype "passive"))
    )
    (net (code "29") (name "D_IN_5") (class "Default")
      (node (ref "CONN10") (pin "9") (pinfunction "9_9") (pintype "passive"))
      (node (ref "R30") (pin "2") (pinfunction "2_2") (pintype "passive"))
      (node (ref "R62") (pin "1") (pinfunction "1_1") (pintype "passive"))
    )
    (net (code "30") (name "D_IN_6") (class "Default")
      (node (ref "CONN10") (pin "11") (pinfunction "11_11") (pintype "passive"))
      (node (ref "R29") (pin "2") (pinfunction "2_2") (pintype "passive"))
      (node (ref "R61") (pin "1") (pinfunction "1_1") (pintype "passive"))
    )
    (net (code "31") (name "D_IN_7") (class "Default")
      (node (ref "CONN10") (pin "13") (pinfunction "13_13") (pintype "passive"))
      (node (ref "R28") (pin "2") (pinfunction "2_2") (pintype "passive"))
      (node (ref "R60") (pin "1") (pinfunction "1_1") (pintype "passive"))
    )
    (net (code "32") (name "D_IN_8") (class "Default")
      (node (ref "CONN10") (pin "15") (pinfunction "15_15") (pintype "passive"))
      (node (ref "R27") (pin "2") (pinfunction "2_2") (pintype "passive"))
      (node (ref "R59") (pin "1") (pinfunction "1_1") (pintype "passive"))
    )
    (net (code "33") (name "D_IN_9") (class "Default")
      (node (ref "CONN15") (pin "1") (pinfunction "1_1") (pintype "passive"))
      (node (ref "R26") (pin "2") (pinfunction "2_2") (pintype "passive"))
      (node (ref "R58") (pin "1") (pinfunction "1_1") (pintype "passive"))
    )
    (net (code "34") (name "D_IN_10") (class "Default")
      (node (ref "CONN15") (pin "3") (pinfunction "3_3") (pintype "passive"))
      (node (ref "R25") (pin "2") (pinfunction "2_2") (pintype "passive"))
      (node (ref "R57") (pin "1") (pinfunction "1_1") (pintype "passive"))
    )
    (net (code "35") (name "D_IN_11") (class "Default")
      (node (ref "CONN15") (pin "5") (pinfunction "5_5") (pintype "passive"))
      (node (ref "R24") (pin "2") (pinfunction "2_2") (pintype "passive"))
      (node (ref "R56") (pin "1") (pinfunction "1_1") (pintype "passive"))
    )
    (net (code "36") (name "D_IN_12") (class "Default")
      (node (ref "CONN15") (pin "7") (pinfunction "7_7") (pintype "passive"))
      (node (ref "R23") (pin "2") (pinfunction "2_2") (pintype "passive"))
      (node (ref "R55") (pin "1") (pinfunction "1_1") (pintype "passive"))
    )
    (net (code "37") (name "D_IN_13") (class "Default")
      (node (ref "CONN15") (pin "9") (pinfunction "9_9") (pintype "passive"))
      (node (ref "R22") (pin "2") (pinfunction "2_2") (pintype "passive"))
      (node (ref "R54") (pin "1") (pinfunction "1_1") (pintype "passive"))
    )
    (net (code "38") (name "D_IN_14") (class "Default")
      (node (ref "CONN15") (pin "11") (pinfunction "11_11") (pintype "passive"))
      (node (ref "R21") (pin "2") (pinfunction "2_2") (pintype "passive"))
      (node (ref "R53") (pin "1") (pinfunction "1_1") (pintype "passive"))
    )
    (net (code "39") (name "D_IN_15") (class "Default")
      (node (ref "CONN15") (pin "13") (pinfunction "13_13") (pintype "passive"))
      (node (ref "R20") (pin "2") (pinfunction "2_2") (pintype "passive"))
      (node (ref "R52") (pin "1") (pinfunction "1_1") (pintype "passive"))
    )
    (net (code "40") (name "D_IN_16") (class "Default")
      (node (ref "CONN15") (pin "15") (pinfunction "15_15") (pintype "passive"))
      (node (ref "R19") (pin "2") (pinfunction "2_2") (pintype "passive"))
      (node (ref "R51") (pin "1") (pinfunction "1_1") (pintype "passive"))
    )
    (net (code "41") (name "D_OUT_1_L") (class "Default")
      (node (ref "CONN9") (pin "1") (pinfunction "1_1") (pintype "passive"))
      (node (ref "R50") (pin "2") (pinfunction "2_2") (pintype "passive"))
    )
    (net (code "42") (name "D_OUT_1_R") (class "Default")
      (node (ref "R50") (pin "1") (pinfunction "1_1") (pintype "passive"))
      (node (ref "U2") (pin "26") (pinfunction "PD1(OC2B/SDA/INT1)_26") (pintype "bidirectional"))
    )
    (net (code "43") (name "D_OUT_2_L") (class "Default")
      (node (ref "CONN9") (pin "3") (pinfunction "3_3") (pintype "passive"))
      (node (ref "R49") (pin "2") (pinfunction "2_2") (pintype "passive"))
    )
    (net (code "44") (name "D_OUT_2_R") (class "Default")
      (node (ref "R49") (pin "1") (pinfunction "1_1") (pintype "passive"))
      (node (ref "U2") (pin "25") (pinfunction "PD0(OC0B/SCL/INT0)_25") (pintype "bidirectional"))
    )
    (net (code "45") (name "D_OUT_3_L") (class "Default")
      (node (ref "CONN9") (pin "5") (pinfunction "5_5") (pintype "passive"))
      (node (ref "R48") (pin "2") (pinfunction "2_2") (pintype "passive"))
    )
    (net (code "46") (name "D_OUT_3_R") (class "Default")
      (node (ref "R48") (pin "1") (pinfunction "1_1") (pintype "passive"))
      (node (ref "U2") (pin "19") (pinfunction "PE5(INT.5/TOSC2)_19") (pintype "bidirectional"))
    )
    (net (code "47") (name "D_OUT_4_L") (class "Default")
      (node (ref "CONN9") (pin "7") (pinfunction "7_7") (pintype "passive"))
      (node (ref "R47") (pin "2") (pinfunction "2_2") (pintype "passive"))
    )
    (net (code "48") (name "D_OUT_4_R") (class "Default")
      (node (ref "R47") (pin "1") (pinfunction "1_1") (pintype "passive"))
      (node (ref "U2") (pin "18") (pinfunction "PE4(INT4/TOSC1)_18") (pintype "bidirectional"))
    )
    (net (code "49") (name "D_OUT_5_L") (class "Default")
      (node (ref "CONN9") (pin "9") (pinfunction "9_9") (pintype "passive"))
      (node (ref "R46") (pin "2") (pinfunction "2_2") (pintype "passive"))
    )
    (net (code "50") (name "D_OUT_5_R") (class "Default")
      (node (ref "R46") (pin "1") (pinfunction "1_1") (pintype "passive"))
      (node (ref "U2") (pin "17") (pinfunction "PB7(PCINT7/OC.1C)_17") (pintype "bidirectional"))
    )
    (net (code "51") (name "D_OUT_6_L") (class "Default")
      (node (ref "CONN9") (pin "11") (pinfunction "11_11") (pintype "passive"))
      (node (ref "R45") (pin "2") (pinfunction "2_2") (pintype "passive"))
    )
    (net (code "52") (name "D_OUT_6_R") (class "Default")
      (node (ref "R45") (pin "1") (pinfunction "1_1") (pintype "passive"))
      (node (ref "U2") (pin "16") (pinfunction "PB6(PCINT6/OC.1B)_16") (pintype "bidirectional"))
    )
    (net (code "53") (name "D_OUT_7_L") (class "Default")
      (node (ref "CONN9") (pin "13") (pinfunction "13_13") (pintype "passive"))
      (node (ref "R44") (pin "2") (pinfunction "2_2") (pintype "passive"))
    )
    (net (code "54") (name "D_OUT_7_R") (class "Default")
      (node (ref "R44") (pin "1") (pinfunction "1_1") (pintype "passive"))
      (node (ref "U2") (pin "15") (pinfunction "PB5(PCINT5/OC.1A)_15") (pintype "bidirectional"))
    )
    (net (code "55") (name "D_OUT_8_L") (class "Default")
      (node (ref "CONN9") (pin "15") (pinfunction "15_15") (pintype "passive"))
      (node (ref "R43") (pin "2") (pinfunction "2_2") (pintype "passive"))
    )
    (net (code "56") (name "D_OUT_8_R") (class "Default")
      (node (ref "R43") (pin "1") (pinfunction "1_1") (pintype "passive"))
      (node (ref "U2") (pin "14") (pinfunction "PB4(PCINT4/OC.2A)_14") (pintype "bidirectional"))
    )
    (net (code "57") (name "D_OUT_9_L") (class "Default")
      (node (ref "CONN16") (pin "1") (pinfunction "1_1") (pintype "passive"))
      (node (ref "R42") (pin "1") (pinfunction "1_1") (pintype "passive"))
    )
    (net (code "58") (name "D_OUT_9_R") (class "Default")
      (node (ref "R42") (pin "2") (pinfunction "2_2") (pintype "passive"))
      (node (ref "U2") (pin "33") (pinfunction "PE0(~{WR})_33") (pintype "bidirectional"))
    )
    (net (code "59") (name "D_OUT_10_L") (class "Default")
      (node (ref "CONN16") (pin "3") (pinfunction "3_3") (pintype "passive"))
      (node (ref "R41") (pin "1") (pinfunction "1_1") (pintype "passive"))
    )
    (net (code "60") (name "D_OUT_10_R") (class "Default")
      (node (ref "R41") (pin "2") (pinfunction "2_2") (pintype "passive"))
      (node (ref "U2") (pin "34") (pinfunction "PE1(~{RD})_34") (pintype "bidirectional"))
    )
    (net (code "61") (name "D_OUT_11_L") (class "Default")
      (node (ref "CONN16") (pin "5") (pinfunction "5_5") (pintype "passive"))
      (node (ref "R40") (pin "1") (pinfunction "1_1") (pintype "passive"))
    )
    (net (code "62") (name "D_OUT_11_R") (class "Default")
      (node (ref "R40") (pin "2") (pinfunction "2_2") (pintype "passive"))
      (node (ref "U2") (pin "35") (pinfunction "PC0(A8)_35") (pintype "bidirectional"))
    )
    (net (code "63") (name "D_OUT_12_L") (class "Default")
      (node (ref "CONN16") (pin "7") (pinfunction "7_7") (pintype "passive"))
      (node (ref "R39") (pin "1") (pinfunction "1_1") (pintype "passive"))
    )
    (net (code "64") (name "D_OUT_12_R") (class "Default")
      (node (ref "R39") (pin "2") (pinfunction "2_2") (pintype "passive"))
      (node (ref "U2") (pin "36") (pinfunction "PC1(A9)_36") (pintype "bidirectional"))
    )
    (net (code "65") (name "D_OUT_13_L") (class "Default")
      (node (ref "CONN16") (pin "9") (pinfunction "9_9") (pintype "passive"))
      (node (ref "R38") (pin "1") (pinfunction "1_1") (pintype "passive"))
    )
    (net (code "66") (name "D_OUT_13_R") (class "Default")
      (node (ref "R38") (pin "2") (pinfunction "2_2") (pintype "passive"))
      (node (ref "U2") (pin "37") (pinfunction "PC2(A10)_37") (pintype "bidirectional"))
    )
    (net (code "67") (name "D_OUT_14_L") (class "Default")
      (node (ref "CONN16") (pin "11") (pinfunction "11_11") (pintype "passive"))
      (node (ref "R37") (pin "1") (pinfunction "1_1") (pintype "passive"))
    )
    (net (code "68") (name "D_OUT_14_R") (class "Default")
      (node (ref "R37") (pin "2") (pinfunction "2_2") (pintype "passive"))
      (node (ref "U2") (pin "38") (pinfunction "PC3(A11/T.3)_38") (pintype "bidirectional"))
    )
    (net (code "69") (name "D_OUT_15_L") (class "Default")
      (node (ref "CONN16") (pin "13") (pinfunction "13_13") (pintype "passive"))
      (node (ref "R36") (pin "1") (pinfunction "1_1") (pintype "passive"))
    )
    (net (code "70") (name "D_OUT_15_R") (class "Default")
      (node (ref "R36") (pin "2") (pinfunction "2_2") (pintype "passive"))
      (node (ref "U2") (pin "39") (pinfunction "PC4(A12/OC.3C)_39") (pintype "bidirectional"))
    )
    (net (code "71") (name "D_OUT_16_L") (class "Default")
      (node (ref "CONN16") (pin "15") (pinfunction "15_15") (pintype "passive"))
      (node (ref "R35") (pin "1") (pinfunction "1_1") (pintype "passive"))
    )
    (net (code "72") (name "D_OUT_16_R") (class "Default")
      (node (ref "R35") (pin "2") (pinfunction "2_2") (pintype "passive"))
      (node (ref "U2") (pin "40") (pinfunction "PC5(A13/OC.3A)_40") (pintype "bidirectional"))
    )
    (net (code "73") (name "D_OUT_17") (class "Default")
      (node (ref "R76") (pin "1") (pinfunction "1_1") (pintype "passive"))
      (node (ref "U2") (pin "31") (pinfunction "PD6(T1)_31") (pintype "bidirectional"))
    )
    (net (code "74") (name "D_OUT_17_HV") (class "Default")
      (node (ref "CONN5") (pin "2") (pinfunction "2_2") (pintype "passive"))
      (node (ref "D14") (pin "3") (pinfunction "A_3") (pintype "passive"))
      (node (ref "Q5") (pin "4") (pinfunction "D_4") (pintype "passive"))
    )
    (net (code "75") (name "D_OUT_18") (class "Default")
      (node (ref "R75") (pin "1") (pinfunction "1_1") (pintype "passive"))
      (node (ref "U2") (pin "32") (pinfunction "PD7(T0)_32") (pintype "bidirectional"))
    )
    (net (code "76") (name "D_OUT_18_HV") (class "Default")
      (node (ref "CONN5") (pin "4") (pinfunction "4_4") (pintype "passive"))
      (node (ref "D14") (pin "4") (pinfunction "A_4") (pintype "passive"))
      (node (ref "Q5") (pin "6") (pinfunction "D_6") (pintype "passive"))
    )
    (net (code "77") (name "D_OUT_19") (class "Default")
      (node (ref "R78") (pin "1") (pinfunction "1_1") (pintype "passive"))
      (node (ref "U2") (pin "29") (pinfunction "PD4(ICP1)_29") (pintype "bidirectional"))
    )
    (net (code "78") (name "D_OUT_19_HV") (class "Default")
      (node (ref "CONN5") (pin "8") (pinfunction "8_8") (pintype "passive"))
      (node (ref "D12") (pin "3") (pinfunction "A_3") (pintype "passive"))
      (node (ref "Q2") (pin "4") (pinfunction "D_4") (pintype "passive"))
    )
    (net (code "79") (name "D_OUT_20") (class "Default")
      (node (ref "R77") (pin "1") (pinfunction "1_1") (pintype "passive"))
      (node (ref "U2") (pin "30") (pinfunction "PD5(XCK1)_30") (pintype "bidirectional"))
    )
    (net (code "80") (name "D_OUT_20_HV") (class "Default")
      (node (ref "CONN5") (pin "6") (pinfunction "6_6") (pintype "passive"))
      (node (ref "D12") (pin "4") (pinfunction "A_4") (pintype "passive"))
      (node (ref "Q2") (pin "6") (pinfunction "D_6") (pintype "passive"))
    )
    (net (code "81") (name "GND") (class "Default")
      (node (ref "C1") (pin "1") (pinfunction "1_1") (pintype "passive"))
      (node (ref "C10") (pin "2") (pinfunction "2_2") (pintype "passive"))
      (node (ref "C11") (pin "1") (pinfunction "1_1") (pintype "passive"))
      (node (ref "C12") (pin "1") (pinfunction "1_1") (pintype "passive"))
      (node (ref "C13") (pin "2") (pinfunction "2_2") (pintype "passive"))
      (node (ref "C14") (pin "1") (pinfunction "1_1") (pintype "passive"))
      (node (ref "C15") (pin "1") (pinfunction "1_1") (pintype "passive"))
      (node (ref "C16") (pin "2") (pinfunction "2_2") (pintype "passive"))
      (node (ref "C17") (pin "2") (pinfunction "2_2") (pintype "passive"))
      (node (ref "C18") (pin "2") (pinfunction "2_2") (pintype "passive"))
      (node (ref "C2") (pin "2") (pinfunction "2_2") (pintype "passive"))
      (node (ref "C3") (pin "2") (pinfunction "2_2") (pintype "passive"))
      (node (ref "C4") (pin "2") (pinfunction "2_2") (pintype "passive"))
      (node (ref "C5") (pin "2") (pinfunction "2_2") (pintype "passive"))
      (node (ref "C6") (pin "2") (pinfunction "2_2") (pintype "passive"))
      (node (ref "C7") (pin "2") (pinfunction "2_2") (pintype "passive"))
      (node (ref "C8") (pin "1") (pinfunction "1_1") (pintype "passive"))
      (node (ref "C9") (pin "2") (pinfunction "2_2") (pintype "passive"))
      (node (ref "CONN10") (pin "10") (pinfunction "10_10") (pintype "passive"))
      (node (ref "CONN10") (pin "12") (pinfunction "12_12") (pintype "passive"))
      (node (ref "CONN10") (pin "14") (pinfunction "14_14") (pintype "passive"))
      (node (ref "CONN10") (pin "16") (pinfunction "16_16") (pintype "passive"))
      (node (ref "CONN10") (pin "2") (pinfunction "2_2") (pintype "passive"))
      (node (ref "CONN10") (pin "4") (pinfunction "4_4") (pintype "passive"))
      (node (ref "CONN10") (pin "6") (pinfunction "6_6") (pintype "passive"))
      (node (ref "CONN10") (pin "8") (pinfunction "8_8") (pintype "passive"))
      (node (ref "CONN13") (pin "1") (pinfunction "1_1") (pintype "passive"))
      (node (ref "CONN13") (pin "2") (pinfunction "2_2") (pintype "passive"))
      (node (ref "CONN13") (pin "3") (pinfunction "3_3") (pintype "passive"))
      (node (ref "CONN13") (pin "4") (pinfunction "4_4") (pintype "passive"))
      (node (ref "CONN13") (pin "5") (pinfunction "5_5") (pintype "passive"))
      (node (ref "CONN13") (pin "6") (pinfunction "6_6") (pintype "passive"))
      (node (ref "CONN13") (pin "7") (pinfunction "7_7") (pintype "passive"))
      (node (ref "CONN13") (pin "8") (pinfunction "8_8") (pintype "passive"))
      (node (ref "CONN14") (pin "1") (pinfunction "1_1") (pintype "passive"))
      (node (ref "CONN14") (pin "2") (pinfunction "2_2") (pintype "passive"))
      (node (ref "CONN14") (pin "3") (pinfunction "3_3") (pintype "passive"))
      (node (ref "CONN14") (pin "4") (pinfunction "4_4") (pintype "passive"))
      (node (ref "CONN14") (pin "5") (pinfunction "5_5") (pintype "passive"))
      (node (ref "CONN14") (pin "6") (pinfunction "6_6") (pintype "passive"))
      (node (ref "CONN14") (pin "7") (pinfunction "7_7") (pintype "passive"))
      (node (ref "CONN14") (pin "8") (pinfunction "8_8") (pintype "passive"))
      (node (ref "CONN15") (pin "10") (pinfunction "10_10") (pintype "passive"))
      (node (ref "CONN15") (pin "12") (pinfunction "12_12") (pintype "passive"))
      (node (ref "CONN15") (pin "14") (pinfunction "14_14") (pintype "passive"))
      (node (ref "CONN15") (pin "16") (pinfunction "16_16") (pintype "passive"))
      (node (ref "CONN15") (pin "2") (pinfunction "2_2") (pintype "passive"))
      (node (ref "CONN15") (pin "4") (pinfunction "4_4") (pintype "passive"))
      (node (ref "CONN15") (pin "6") (pinfunction "6_6") (pintype "passive"))
      (node (ref "CONN15") (pin "8") (pinfunction "8_8") (pintype "passive"))
      (node (ref "CONN16") (pin "10") (pinfunction "10_10") (pintype "passive"))
      (node (ref "CONN16") (pin "12") (pinfunction "12_12") (pintype "passive"))
      (node (ref "CONN16") (pin "14") (pinfunction "14_14") (pintype "passive"))
      (node (ref "CONN16") (pin "16") (pinfunction "16_16") (pintype "passive"))
      (node (ref "CONN16") (pin "2") (pinfunction "2_2") (pintype "passive"))
      (node (ref "CONN16") (pin "4") (pinfunction "4_4") (pintype "passive"))
      (node (ref "CONN16") (pin "6") (pinfunction "6_6") (pintype "passive"))
      (node (ref "CONN16") (pin "8") (pinfunction "8_8") (pintype "passive"))
      (node (ref "CONN2") (pin "2") (pinfunction "2_2") (pintype "passive"))
      (node (ref "CONN9") (pin "10") (pinfunction "10_10") (pintype "passive"))
      (node (ref "CONN9") (pin "12") (pinfunction "12_12") (pintype "passive"))
      (node (ref "CONN9") (pin "14") (pinfunction "14_14") (pintype "passive"))
      (node (ref "CONN9") (pin "16") (pinfunction "16_16") (pintype "passive"))
      (node (ref "CONN9") (pin "2") (pinfunction "2_2") (pintype "passive"))
      (node (ref "CONN9") (pin "4") (pinfunction "4_4") (pintype "passive"))
      (node (ref "CONN9") (pin "6") (pinfunction "6_6") (pintype "passive"))
      (node (ref "CONN9") (pin "8") (pinfunction "8_8") (pintype "passive"))
      (node (ref "D10") (pin "C") (pinfunction "C_C") (pintype "passive"))
      (node (ref "D11") (pin "C") (pinfunction "C_C") (pintype "passive"))
      (node (ref "D2") (pin "1") (pinfunction "GND_1") (pintype "passive"))
      (node (ref "D6") (pin "C") (pinfunction "C_C") (pintype "passive"))
      (node (ref "D7") (pin "C") (pinfunction "C_C") (pintype "passive"))
      (node (ref "D8") (pin "C") (pinfunction "C_C") (pintype "passive"))
      (node (ref "D9") (pin "C") (pinfunction "C_C") (pintype "passive"))
      (node (ref "EXT") (pin "GND@1") (pinfunction "GND_GND@1") (pintype "bidirectional"))
      (node (ref "EXT") (pin "GND@2") (pinfunction "GNDBREAK_GND@2") (pintype "bidirectional"))
      (node (ref "ICSP") (pin "6") (pinfunction "6_6") (pintype "passive"))
      (node (ref "L1") (pin "1") (pinfunction "1_1") (pintype "passive"))
      (node (ref "Q1") (pin "1") (pinfunction "G_1") (pintype "passive"))
      (node (ref "Q2") (pin "2") (pinfunction "S_2") (pintype "passive"))
      (node (ref "Q2") (pin "5") (pinfunction "S_5") (pintype "passive"))
      (node (ref "Q5") (pin "2") (pinfunction "S_2") (pintype "passive"))
      (node (ref "Q5") (pin "5") (pinfunction "S_5") (pintype "passive"))
      (node (ref "R12") (pin "2") (pinfunction "2_2") (pintype "passive"))
      (node (ref "R67") (pin "2") (pinfunction "2_2") (pintype "passive"))
      (node (ref "R68") (pin "2") (pinfunction "2_2") (pintype "passive"))
      (node (ref "R69") (pin "2") (pinfunction "2_2") (pintype "passive"))
      (node (ref "R70") (pin "2") (pinfunction "2_2") (pintype "passive"))
      (node (ref "R71") (pin "1") (pinfunction "1_1") (pintype "passive"))
      (node (ref "R72") (pin "1") (pinfunction "1_1") (pintype "passive"))
      (node (ref "TSCREEN") (pin "2") (pinfunction "2_2") (pintype "passive"))
      (node (ref "U1") (pin "5") (pinfunction "GND_5") (pintype "power_in"))
      (node (ref "U2") (pin "22") (pinfunction "GND_22") (pintype "power_in"))
      (node (ref "U2") (pin "53") (pinfunction "GND_53") (pintype "power_in"))
      (node (ref "U2") (pin "6") (pinfunction "UGND_6") (pintype "power_in"))
      (node (ref "U2") (pin "63") (pinfunction "GND_63") (pintype "power_in"))
      (node (ref "U3") (pin "12") (pinfunction "GND_12") (pintype "passive"))
      (node (ref "U3") (pin "15") (pinfunction "~{E}_15") (pintype "input"))
      (node (ref "U4") (pin "15") (pinfunction "~{CE}_15") (pintype "input"))
      (node (ref "U4") (pin "8") (pinfunction "GND_8") (pintype "power_in"))
      (node (ref "U5") (pin "15") (pinfunction "~{CE}_15") (pintype "input"))
      (node (ref "U5") (pin "8") (pinfunction "GND_8") (pintype "power_in"))
      (node (ref "USB") (pin "A1") (pinfunction "GND_A1") (pintype "passive"))
      (node (ref "USB") (pin "A12") (pinfunction "GND_A12") (pintype "passive"))
      (node (ref "USB") (pin "B1") (pinfunction "GND_B1") (pintype "passive"))
      (node (ref "USB") (pin "B12") (pinfunction "GND_B12") (pintype "passive"))
      (node (ref "VR1") (pin "1") (pinfunction "GND_1") (pintype "passive"))
      (node (ref "VR2") (pin "2") (pinfunction "GND_2") (pintype "passive"))
    )
    (net (code "82") (name "LED_IND_DIN_IN") (class "Default")
      (node (ref "R16") (pin "1") (pinfunction "1_1") (pintype "passive"))
      (node (ref "U2") (pin "46") (pinfunction "PA5(AD5)_46") (pintype "bidirectional"))
    )
    (net (code "83") (name "LED_IND_DIN_OUT") (class "Default")
      (node (ref "R15") (pin "1") (pinfunction "1_1") (pintype "passive"))
      (node (ref "U2") (pin "45") (pinfunction "PA6(AD6)_45") (pintype "bidirectional"))
    )
    (net (code "84") (name "LED_IND_USB_IN") (class "Default")
      (node (ref "R18") (pin "1") (pinfunction "1_1") (pintype "passive"))
      (node (ref "U2") (pin "48") (pinfunction "PA3(AD3)_48") (pintype "bidirectional"))
    )
    (net (code "85") (name "LED_IND_USB_OUT") (class "Default")
      (node (ref "R17") (pin "1") (pinfunction "1_1") (pintype "passive"))
      (node (ref "U2") (pin "47") (pinfunction "PA4(AD4)_47") (pintype "bidirectional"))
    )
    (net (code "86") (name "MISO") (class "Default")
      (node (ref "ICSP") (pin "1") (pinfunction "1_1") (pintype "passive"))
      (node (ref "U2") (pin "13") (pinfunction "PB3(PDO/PCINT3/MISO)_13") (pintype "bidirectional"))
    )
    (net (code "87") (name "MOSI") (class "Default")
      (node (ref "ICSP") (pin "4") (pinfunction "4_4") (pintype "passive"))
      (node (ref "U2") (pin "12") (pinfunction "PB2(PDI/PCINT2/MOSI)_12") (pintype "bidirectional"))
    )
    (net (code "88") (name "MUX_COMMON") (class "Default")
      (node (ref "R10") (pin "2") (pinfunction "2_2") (pintype "passive"))
      (node (ref "U3") (pin "1") (pinfunction "Z_1") (pintype "bidirectional"))
    )
    (net (code "89") (name "MUX_S0") (class "Default")
      (node (ref "U2") (pin "41") (pinfunction "PC6(A14/OC.3A)_41") (pintype "bidirectional"))
      (node (ref "U3") (pin "10") (pinfunction "S0_10") (pintype "input"))
    )
    (net (code "90") (name "MUX_S1") (class "Default")
      (node (ref "U2") (pin "42") (pinfunction "PC7(A15/IC.3/CLKO)_42") (pintype "bidirectional"))
      (node (ref "U3") (pin "11") (pinfunction "S1_11") (pintype "input"))
    )
    (net (code "91") (name "MUX_S2") (class "Default")
      (node (ref "U2") (pin "43") (pinfunction "PE2(ALE/~{HWB})_43") (pintype "bidirectional"))
      (node (ref "U3") (pin "14") (pinfunction "S2_14") (pintype "input"))
    )
    (net (code "92") (name "MUX_S3") (class "Default")
      (node (ref "U2") (pin "44") (pinfunction "PA7(AD7)_44") (pintype "bidirectional"))
      (node (ref "U3") (pin "13") (pinfunction "S3_13") (pintype "input"))
    )
    (net (code "93") (name "Net-(CONN2-Pad4)") (class "Default")
      (node (ref "CONN2") (pin "4") (pinfunction "4_4") (pintype "bidirectional"))
      (node (ref "R4") (pin "1") (pinfunction "1_1") (pintype "passive"))
    )
    (net (code "94") (name "Net-(CONN2-Pad5)") (class "Default")
      (node (ref "CONN2") (pin "5") (pinfunction "5_5") (pintype "bidirectional"))
      (node (ref "R3") (pin "1") (pinfunction "1_1") (pintype "passive"))
    )
    (net (code "95") (name "Net-(CONN3-Pad4)") (class "Default")
      (node (ref "CONN3") (pin "4") (pinfunction "4_4") (pintype "bidirectional"))
      (node (ref "R5") (pin "1") (pinfunction "1_1") (pintype "passive"))
    )
    (net (code "96") (name "Net-(D5-A)") (class "Default")
      (node (ref "D5") (pin "1") (pinfunction "A_1") (pintype "passive"))
      (node (ref "R10") (pin "1") (pinfunction "1_1") (pintype "passive"))
      (node (ref "U2") (pin "61") (pinfunction "PF0(ADC0)_61") (pintype "bidirectional"))
    )
    (net (code "97") (name "Net-(D6-PadA)") (class "Default")
      (node (ref "D6") (pin "A") (pinfunction "A_A") (pintype "passive"))
      (node (ref "R13") (pin "2") (pinfunction "2_2") (pintype "passive"))
    )
    (net (code "98") (name "Net-(D7-PadA)") (class "Default")
      (node (ref "D7") (pin "A") (pinfunction "A_A") (pintype "passive"))
      (node (ref "R14") (pin "2") (pinfunction "2_2") (pintype "passive"))
    )
    (net (code "99") (name "Net-(D8-PadA)") (class "Default")
      (node (ref "D8") (pin "A") (pinfunction "A_A") (pintype "passive"))
      (node (ref "R15") (pin "2") (pinfunction "2_2") (pintype "passive"))
    )
    (net (code "100") (name "Net-(D9-PadA)") (class "Default")
      (node (ref "D9") (pin "A") (pinfunction "A_A") (pintype "passive"))
      (node (ref "R16") (pin "2") (pinfunction "2_2") (pintype "passive"))
    )
    (net (code "101") (name "Net-(D10-PadA)") (class "Default")
      (node (ref "D10") (pin "A") (pinfunction "A_A") (pintype "passive"))
      (node (ref "R17") (pin "2") (pinfunction "2_2") (pintype "passive"))
    )
    (net (code "102") (name "Net-(D11-PadA)") (class "Default")
      (node (ref "D11") (pin "A") (pinfunction "A_A") (pintype "passive"))
      (node (ref "R18") (pin "2") (pinfunction "2_2") (pintype "passive"))
    )
    (net (code "103") (name "Net-(EXT-PWR)") (class "Default")
      (node (ref "EXT") (pin "PWR1") (pinfunction "PWR_PWR1") (pintype "bidirectional"))
      (node (ref "Q1") (pin "2") (pinfunction "S_2") (pintype "passive"))
    )
    (net (code "104") (name "Net-(F1-Pad2)") (class "Default")
      (node (ref "F1") (pin "2") (pinfunction "2_2") (pintype "passive"))
      (node (ref "USB") (pin "A4") (pinfunction "VBUS_A4") (pintype "power_in"))
      (node (ref "USB") (pin "A9") (pinfunction "VBUS_A9") (pintype "power_in"))
      (node (ref "USB") (pin "B4") (pinfunction "VBUS_B4") (pintype "power_in"))
      (node (ref "USB") (pin "B9") (pinfunction "VBUS_B9") (pintype "power_in"))
    )
    (net (code "105") (name "Net-(L1-Pad2)") (class "Default")
      (node (ref "L1") (pin "2") (pinfunction "2_2") (pintype "passive"))
      (node (ref "USB") (pin "P1") (pinfunction "SHIELD_P1") (pintype "passive"))
      (node (ref "USB") (pin "P2") (pinfunction "SHIELD_P2") (pintype "passive"))
      (node (ref "USB") (pin "P3") (pinfunction "SHIELD_P3") (pintype "passive"))
      (node (ref "USB") (pin "P4") (pinfunction "SHIELD_P4") (pintype "passive"))
    )
    (net (code "106") (name "Net-(Q2A-G)") (class "Default")
      (node (ref "Q2") (pin "1") (pinfunction "G_1") (pintype "passive"))
      (node (ref "R68") (pin "1") (pinfunction "1_1") (pintype "passive"))
      (node (ref "R77") (pin "2") (pinfunction "2_2") (pintype "passive"))
    )
    (net (code "107") (name "Net-(Q2B-G)") (class "Default")
      (node (ref "Q2") (pin "3") (pinfunction "G_3") (pintype "passive"))
      (node (ref "R67") (pin "1") (pinfunction "1_1") (pintype "passive"))
      (node (ref "R78") (pin "2") (pinfunction "2_2") (pintype "passive"))
    )
    (net (code "108") (name "Net-(Q5A-G)") (class "Default")
      (node (ref "Q5") (pin "1") (pinfunction "G_1") (pintype "passive"))
      (node (ref "R70") (pin "1") (pinfunction "1_1") (pintype "passive"))
      (node (ref "R75") (pin "2") (pinfunction "2_2") (pintype "passive"))
    )
    (net (code "109") (name "Net-(Q5B-G)") (class "Default")
      (node (ref "Q5") (pin "3") (pinfunction "G_3") (pintype "passive"))
      (node (ref "R69") (pin "1") (pinfunction "1_1") (pintype "passive"))
      (node (ref "R76") (pin "2") (pinfunction "2_2") (pintype "passive"))
    )
    (net (code "110") (name "Net-(R3-Pad2)") (class "Default")
      (node (ref "R3") (pin "2") (pinfunction "2_2") (pintype "passive"))
      (node (ref "R6") (pin "1") (pinfunction "1_1") (pintype "passive"))
    )
    (net (code "111") (name "Net-(U1-A)") (class "Default")
      (node (ref "D1") (pin "C") (pinfunction "C_C") (pintype "passive"))
      (node (ref "R5") (pin "2") (pinfunction "2_2") (pintype "passive"))
      (node (ref "U1") (pin "2") (pinfunction "A_2") (pintype "passive"))
    )
    (net (code "112") (name "Net-(U1-C)") (class "Default")
      (node (ref "CONN3") (pin "5") (pinfunction "5_5") (pintype "bidirectional"))
      (node (ref "D1") (pin "A") (pinfunction "A_A") (pintype "passive"))
      (node (ref "U1") (pin "3") (pinfunction "C_3") (pintype "passive"))
    )
    (net (code "113") (name "Net-(U1-VO)") (class "Default")
      (node (ref "R8") (pin "2") (pinfunction "2_2") (pintype "passive"))
      (node (ref "R9") (pin "1") (pinfunction "1_1") (pintype "passive"))
      (node (ref "U1") (pin "6") (pinfunction "VO_6") (pintype "output"))
    )
    (net (code "114") (name "Net-(U2-UCAP)") (class "Default")
      (node (ref "C11") (pin "2") (pinfunction "2_2") (pintype "passive"))
      (node (ref "U2") (pin "7") (pinfunction "UCAP_7") (pintype "bidirectional"))
    )
    (net (code "115") (name "Net-(U4-D0)") (class "Default")
      (node (ref "R23") (pin "1") (pinfunction "1_1") (pintype "passive"))
      (node (ref "U4") (pin "11") (pinfunction "D0_11") (pintype "input"))
    )
    (net (code "116") (name "Net-(U4-D1)") (class "Default")
      (node (ref "R24") (pin "1") (pinfunction "1_1") (pintype "passive"))
      (node (ref "U4") (pin "12") (pinfunction "D1_12") (pintype "input"))
    )
    (net (code "117") (name "Net-(U4-D2)") (class "Default")
      (node (ref "R25") (pin "1") (pinfunction "1_1") (pintype "passive"))
      (node (ref "U4") (pin "13") (pinfunction "D2_13") (pintype "input"))
    )
    (net (code "118") (name "Net-(U4-D3)") (class "Default")
      (node (ref "R26") (pin "1") (pinfunction "1_1") (pintype "passive"))
      (node (ref "U4") (pin "14") (pinfunction "D3_14") (pintype "input"))
    )
    (net (code "119") (name "Net-(U4-D4)") (class "Default")
      (node (ref "R22") (pin "1") (pinfunction "1_1") (pintype "passive"))
      (node (ref "U4") (pin "3") (pinfunction "D4_3") (pintype "input"))
    )
    (net (code "120") (name "Net-(U4-D5)") (class "Default")
      (node (ref "R21") (pin "1") (pinfunction "1_1") (pintype "passive"))
      (node (ref "U4") (pin "4") (pinfunction "D5_4") (pintype "input"))
    )
    (net (code "121") (name "Net-(U4-D6)") (class "Default")
      (node (ref "R20") (pin "1") (pinfunction "1_1") (pintype "passive"))
      (node (ref "U4") (pin "5") (pinfunction "D6_5") (pintype "input"))
    )
    (net (code "122") (name "Net-(U4-D7)") (class "Default")
      (node (ref "R19") (pin "1") (pinfunction "1_1") (pintype "passive"))
      (node (ref "U4") (pin "6") (pinfunction "D7_6") (pintype "input"))
    )
    (net (code "123") (name "Net-(U5-D0)") (class "Default")
      (node (ref "R31") (pin "1") (pinfunction "1_1") (pintype "passive"))
      (node (ref "U5") (pin "11") (pinfunction "D0_11") (pintype "input"))
    )
    (net (code "124") (name "Net-(U5-D1)") (class "Default")
      (node (ref "R32") (pin "1") (pinfunction "1_1") (pintype "passive"))
      (node (ref "U5") (pin "12") (pinfunction "D1_12") (pintype "input"))
    )
    (net (code "125") (name "Net-(U5-D2)") (class "Default")
      (node (ref "R33") (pin "1") (pinfunction "1_1") (pintype "passive"))
      (node (ref "U5") (pin "13") (pinfunction "D2_13") (pintype "input"))
    )
    (net (code "126") (name "Net-(U5-D3)") (class "Default")
      (node (ref "R34") (pin "1") (pinfunction "1_1") (pintype "passive"))
      (node (ref "U5") (pin "14") (pinfunction "D3_14") (pintype "input"))
    )
    (net (code "127") (name "Net-(U5-D4)") (class "Default")
      (node (ref "R30") (pin "1") (pinfunction "1_1") (pintype "passive"))
      (node (ref "U5") (pin "3") (pinfunction "D4_3") (pintype "input"))
    )
    (net (code "128") (name "Net-(U5-D5)") (class "Default")
      (node (ref "R29") (pin "1") (pinfunction "1_1") (pintype "passive"))
      (node (ref "U5") (pin "4") (pinfunction "D5_4") (pintype "input"))
    )
    (net (code "129") (name "Net-(U5-D6)") (class "Default")
      (node (ref "R28") (pin "1") (pinfunction "1_1") (pintype "passive"))
      (node (ref "U5") (pin "5") (pinfunction "D6_5") (pintype "input"))
    )
    (net (code "130") (name "Net-(U5-D7)") (class "Default")
      (node (ref "R27") (pin "1") (pinfunction "1_1") (pintype "passive"))
      (node (ref "U5") (pin "6") (pinfunction "D7_6") (pintype "input"))
    )
    (net (code "131") (name "Net-(USB-CC1)") (class "Default")
      (node (ref "R71") (pin "2") (pinfunction "2_2") (pintype "passive"))
      (node (ref "USB") (pin "A5") (pinfunction "CC1_A5") (pintype "bidirectional"))
    )
    (net (code "132") (name "Net-(USB-CC2)") (class "Default")
      (node (ref "R72") (pin "2") (pinfunction "2_2") (pintype "passive"))
      (node (ref "USB") (pin "B5") (pinfunction "CC2_B5") (pintype "bidirectional"))
    )
    (net (code "133") (name "RESET") (class "Default")
      (node (ref "ICSP") (pin "5") (pinfunction "5_5") (pintype "passive"))
      (node (ref "R7") (pin "1") (pinfunction "1_1") (pintype "passive"))
      (node (ref "U2") (pin "20") (pinfunction "~{RESET}_20") (pintype "bidirectional"))
    )
    (net (code "134") (name "SCK") (class "Default")
      (node (ref "ICSP") (pin "3") (pinfunction "3_3") (pintype "passive"))
      (node (ref "U2") (pin "11") (pinfunction "PB1(PCINT1/SCLK)_11") (pintype "bidirectional"))
    )
    (net (code "135") (name "SR_IN_CLOCK") (class "Default")
      (node (ref "U2") (pin "10") (pinfunction "PB0(SS/PCINT0)_10") (pintype "bidirectional"))
      (node (ref "U4") (pin "2") (pinfunction "CP_2") (pintype "bidirectional"))
      (node (ref "U5") (pin "2") (pinfunction "CP_2") (pintype "bidirectional"))
    )
    (net (code "136") (name "SR_IN_DAISY_OUT_1") (class "Default")
      (node (ref "U4") (pin "9") (pinfunction "Q7_9") (pintype "output"))
      (node (ref "U5") (pin "10") (pinfunction "DS_10") (pintype "bidirectional"))
    )
    (net (code "137") (name "SR_IN_DATA") (class "Default")
      (node (ref "U2") (pin "1") (pinfunction "PE6(INT.6/AIN.0)_1") (pintype "bidirectional"))
      (node (ref "U5") (pin "9") (pinfunction "Q7_9") (pintype "output"))
    )
    (net (code "138") (name "SR_IN_LATCH") (class "Default")
      (node (ref "U2") (pin "2") (pinfunction "PE7(INT.7/AIN.1/UVCON)_2") (pintype "bidirectional"))
      (node (ref "U4") (pin "1") (pinfunction "~{PL}_1") (pintype "input"))
      (node (ref "U5") (pin "1") (pinfunction "~{PL}_1") (pintype "input"))
    )
    (net (code "139") (name "UART_RX") (class "Default")
      (node (ref "R8") (pin "1") (pinfunction "1_1") (pintype "passive"))
      (node (ref "TSCREEN") (pin "4") (pinfunction "4_4") (pintype "passive"))
      (node (ref "U2") (pin "27") (pinfunction "PD2(RXD1/INT2)_27") (pintype "bidirectional"))
    )
    (net (code "140") (name "UART_TX") (class "Default")
      (node (ref "R6") (pin "2") (pinfunction "2_2") (pintype "passive"))
      (node (ref "TSCREEN") (pin "3") (pinfunction "3_3") (pintype "passive"))
      (node (ref "U2") (pin "28") (pinfunction "PD3(TXD1/INT3)_28") (pintype "bidirectional"))
    )
    (net (code "141") (name "VIN") (class "Default")
      (node (ref "C10") (pin "1") (pinfunction "1_1") (pintype "passive"))
      (node (ref "CONN5") (pin "1") (pinfunction "1_1") (pintype "passive"))
      (node (ref "CONN5") (pin "3") (pinfunction "3_3") (pintype "passive"))
      (node (ref "CONN5") (pin "5") (pinfunction "5_5") (pintype "passive"))
      (node (ref "CONN5") (pin "7") (pinfunction "7_7") (pintype "passive"))
      (node (ref "D12") (pin "1") (pinfunction "C_1") (pintype "passive"))
      (node (ref "D12") (pin "2") (pinfunction "C_2") (pintype "passive"))
      (node (ref "D14") (pin "1") (pinfunction "C_1") (pintype "passive"))
      (node (ref "D14") (pin "2") (pinfunction "C_2") (pintype "passive"))
      (node (ref "Q1") (pin "3") (pinfunction "D_3") (pintype "passive"))
      (node (ref "VR1") (pin "3") (pinfunction "VIN_3") (pintype "passive"))
    )
    (net (code "142") (name "VUSB") (class "Default")
      (node (ref "C7") (pin "1") (pinfunction "1_1") (pintype "passive"))
      (node (ref "C9") (pin "1") (pinfunction "1_1") (pintype "passive"))
      (node (ref "D2") (pin "4") (pinfunction "VCC_4") (pintype "passive"))
      (node (ref "D3") (pin "A") (pinfunction "A_A") (pintype "passive"))
      (node (ref "F1") (pin "1") (pinfunction "1_1") (pintype "passive"))
      (node (ref "R14") (pin "1") (pinfunction "1_1") (pintype "passive"))
    )
    (net (code "143") (name "XTAL1") (class "Default")
      (node (ref "C1") (pin "2") (pinfunction "2_2") (pintype "passive"))
      (node (ref "U2") (pin "24") (pinfunction "XTAL1_24") (pintype "input"))
      (node (ref "Y1") (pin "1") (pinfunction "1_1") (pintype "passive"))
    )
    (net (code "144") (name "XTAL2") (class "Default")
      (node (ref "C8") (pin "2") (pinfunction "2_2") (pintype "passive"))
      (node (ref "U2") (pin "23") (pinfunction "XTAL2_23") (pintype "input"))
      (node (ref "Y1") (pin "3") (pinfunction "2_3") (pintype "passive"))
    )
    (net (code "145") (name "unconnected-(CONN2-Pad1)") (class "Default")
      (node (ref "CONN2") (pin "1") (pinfunction "1_1") (pintype "bidirectional"))
    )
    (net (code "146") (name "unconnected-(CONN2-Pad3)") (class "Default")
      (node (ref "CONN2") (pin "3") (pinfunction "3_3") (pintype "bidirectional"))
    )
    (net (code "147") (name "unconnected-(CONN3-Pad1)") (class "Default")
      (node (ref "CONN3") (pin "1") (pinfunction "1_1") (pintype "bidirectional"))
    )
    (net (code "148") (name "unconnected-(CONN3-Pad2)") (class "Default")
      (node (ref "CONN3") (pin "2") (pinfunction "2_2") (pintype "passive"))
    )
    (net (code "149") (name "unconnected-(CONN3-Pad3)") (class "Default")
      (node (ref "CONN3") (pin "3") (pinfunction "3_3") (pintype "bidirectional"))
    )
    (net (code "150") (name "unconnected-(U2-PA0(AD0)-Pad51)") (class "Default")
      (node (ref "U2") (pin "51") (pinfunction "PA0(AD0)_51") (pintype "bidirectional"))
    )
    (net (code "151") (name "unconnected-(U2-PA1(AD1)-Pad50)") (class "Default")
      (node (ref "U2") (pin "50") (pinfunction "PA1(AD1)_50") (pintype "bidirectional"))
    )
    (net (code "152") (name "unconnected-(U2-PA2(AD2)-Pad49)") (class "Default")
      (node (ref "U2") (pin "49") (pinfunction "PA2(AD2)_49") (pintype "bidirectional"))
    )
    (net (code "153") (name "unconnected-(U2-PF1(ADC1)-Pad60)") (class "Default")
      (node (ref "U2") (pin "60") (pinfunction "PF1(ADC1)_60") (pintype "bidirectional"))
    )
    (net (code "154") (name "unconnected-(U2-PF2(ADC2)-Pad59)") (class "Default")
      (node (ref "U2") (pin "59") (pinfunction "PF2(ADC2)_59") (pintype "bidirectional"))
    )
    (net (code "155") (name "unconnected-(U2-PF3(ADC3)-Pad58)") (class "Default")
      (node (ref "U2") (pin "58") (pinfunction "PF3(ADC3)_58") (pintype "bidirectional"))
    )
    (net (code "156") (name "unconnected-(U2-PF4(ADC4{slash}TCK)-Pad57)") (class "Default")
      (node (ref "U2") (pin "57") (pinfunction "PF4(ADC4/TCK)_57") (pintype "bidirectional"))
    )
    (net (code "157") (name "unconnected-(U2-PF5(ADC5{slash}TMS)-Pad56)") (class "Default")
      (node (ref "U2") (pin "56") (pinfunction "PF5(ADC5/TMS)_56") (pintype "bidirectional"))
    )
    (net (code "158") (name "unconnected-(U2-PF6(ADC6{slash}TDO)-Pad55)") (class "Default")
      (node (ref "U2") (pin "55") (pinfunction "PF6(ADC6/TDO)_55") (pintype "bidirectional"))
    )
    (net (code "159") (name "unconnected-(U2-PF7(ADC7{slash}TDI)-Pad54)") (class "Default")
      (node (ref "U2") (pin "54") (pinfunction "PF7(ADC7/TDI)_54") (pintype "bidirectional"))
    )
    (net (code "160") (name "unconnected-(U4-DS-Pad10)") (class "Default")
      (node (ref "U4") (pin "10") (pinfunction "DS_10") (pintype "bidirectional"))
    )
    (net (code "161") (name "unconnected-(U4-~{Q7}-Pad7)") (class "Default")
      (node (ref "U4") (pin "7") (pinfunction "~{Q7}_7") (pintype "output"))
    )
    (net (code "162") (name "unconnected-(U5-~{Q7}-Pad7)") (class "Default")
      (node (ref "U5") (pin "7") (pinfunction "~{Q7}_7") (pintype "output"))
    )
    (net (code "163") (name "unconnected-(USB-SBU1-PadA8)") (class "Default")
      (node (ref "USB") (pin "A8") (pinfunction "SBU1_A8") (pintype "bidirectional"))
    )
    (net (code "164") (name "unconnected-(USB-SBU2-PadB8)") (class "Default")
      (node (ref "USB") (pin "B8") (pinfunction "SBU2_B8") (pintype "bidirectional"))
    )
  )
)
